# Armor_Plate_V2_1.net
KiCad netlist of a schematic drawn in Altium Designer
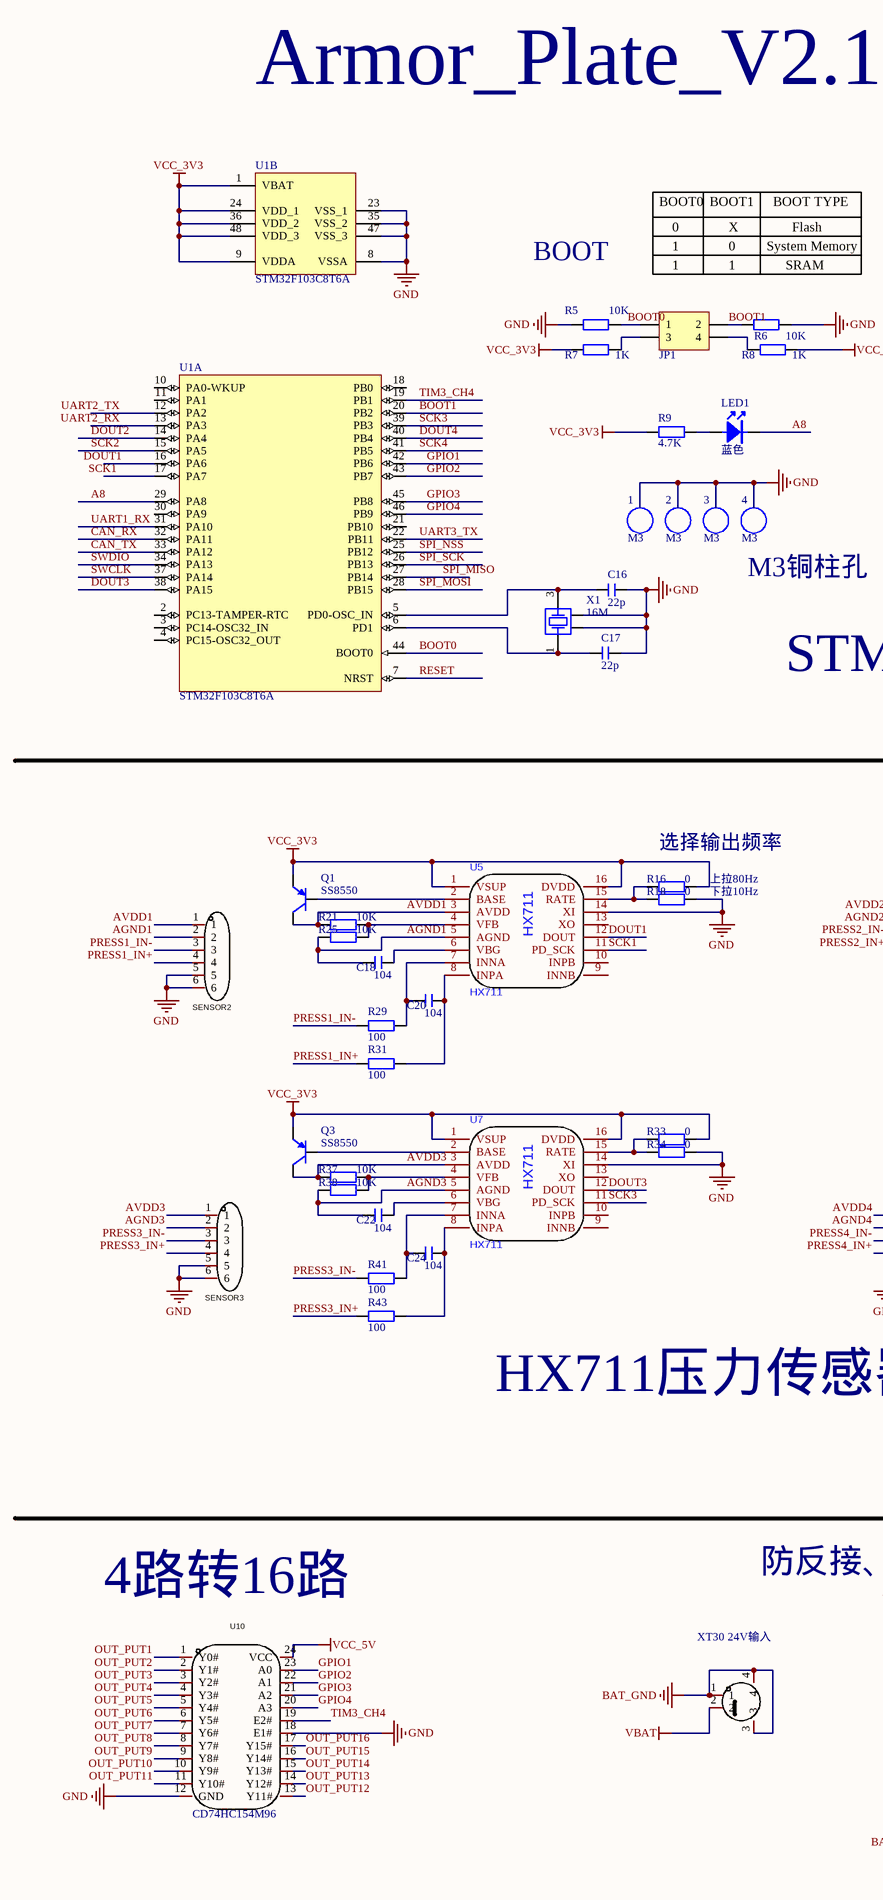
[diagram p0: Armor_Plate_V2.1.SchDoc, left]
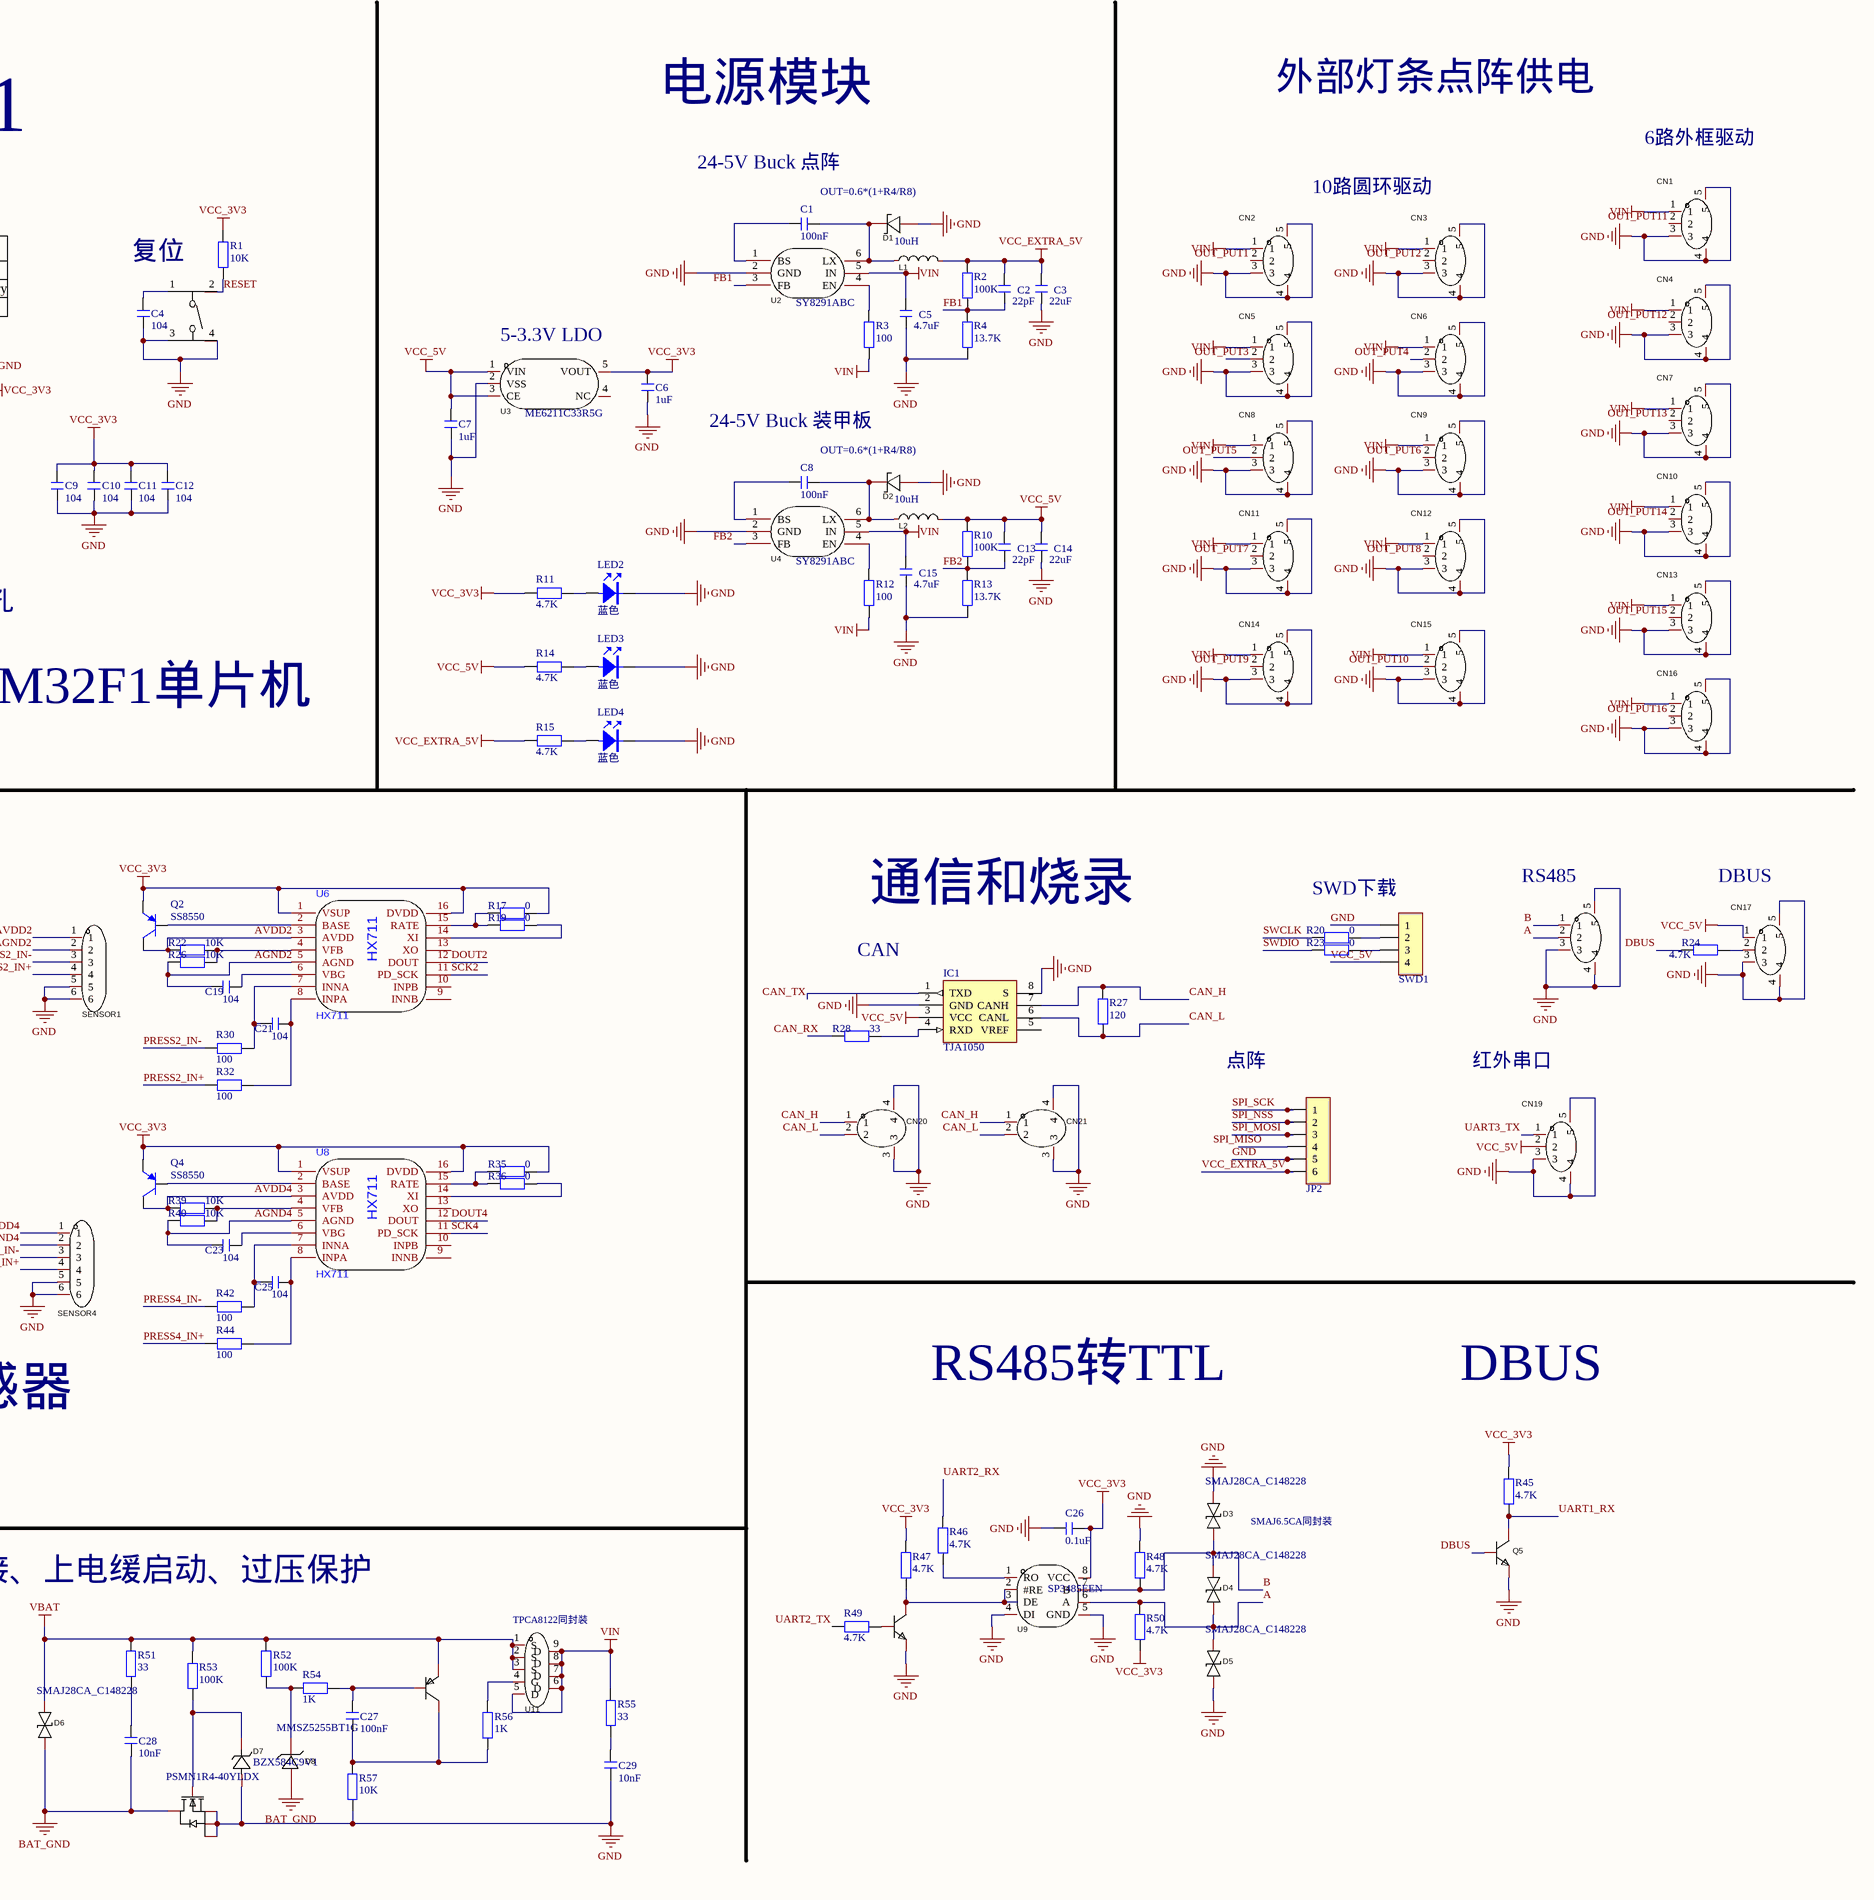
[diagram p1: Armor_Plate_V2.1.SchDoc, right]

(export (version "E")
  (design (tool "Eeschema 10.0.6"))
  (components
    (comp (ref "1")
      (value "M3")
      (footprint "M3 125X200")
      (description "铜柱孔")
      (libsource (lib "10 - 未分类元器件") (part "M3"))
    )
    (comp (ref "2")
      (value "M3")
      (footprint "M3 125X200")
      (description "铜柱孔")
      (libsource (lib "10 - 未分类元器件") (part "M3"))
    )
    (comp (ref "3")
      (value "M3")
      (footprint "M3 125X200")
      (description "铜柱孔")
      (libsource (lib "10 - 未分类元器件") (part "M3"))
    )
    (comp (ref "4")
      (value "M3")
      (footprint "M3 125X200")
      (description "铜柱孔")
      (libsource (lib "10 - 未分类元器件") (part "M3"))
    )
    (comp (ref "C1")
      (value "100nF")
      (footprint "C 0603_L")
      (description "贴片电容")
      (libsource (lib "01 - 电容-电阻-电感") (part "C"))
    )
    (comp (ref "C2")
      (value "22pF")
      (footprint "C 0603_L")
      (description "贴片电容")
      (libsource (lib "01 - 电容-电阻-电感") (part "C"))
    )
    (comp (ref "C3")
      (value "22uF")
      (footprint "C 0603_L")
      (description "贴片电容")
      (libsource (lib "01 - 电容-电阻-电感") (part "C"))
    )
    (comp (ref "C4")
      (value "104")
      (footprint "C 0603_L")
      (description "贴片电容")
      (libsource (lib "01 - 电容-电阻-电感") (part "C"))
    )
    (comp (ref "C5")
      (value "4.7uF")
      (footprint "C 0603_L")
      (description "贴片电容")
      (libsource (lib "01 - 电容-电阻-电感") (part "C"))
    )
    (comp (ref "C6")
      (value "1uF")
      (footprint "C 0603_L")
      (description "贴片电容")
      (libsource (lib "01 - 电容-电阻-电感") (part "C"))
    )
    (comp (ref "C7")
      (value "1uF")
      (footprint "C 0603_L")
      (description "贴片电容")
      (libsource (lib "01 - 电容-电阻-电感") (part "C"))
    )
    (comp (ref "C8")
      (value "100nF")
      (footprint "C 0603_L")
      (description "贴片电容")
      (libsource (lib "01 - 电容-电阻-电感") (part "C"))
    )
    (comp (ref "C9")
      (value "104")
      (footprint "C 0603_L")
      (description "贴片电容")
      (libsource (lib "01 - 电容-电阻-电感") (part "C"))
    )
    (comp (ref "C10")
      (value "104")
      (footprint "C 0603_L")
      (description "贴片电容")
      (libsource (lib "01 - 电容-电阻-电感") (part "C"))
    )
    (comp (ref "C11")
      (value "104")
      (footprint "C 0603_L")
      (description "贴片电容")
      (libsource (lib "01 - 电容-电阻-电感") (part "C"))
    )
    (comp (ref "C12")
      (value "104")
      (footprint "C 0603_L")
      (description "贴片电容")
      (libsource (lib "01 - 电容-电阻-电感") (part "C"))
    )
    (comp (ref "C13")
      (value "22pF")
      (footprint "C 0603_L")
      (description "贴片电容")
      (libsource (lib "01 - 电容-电阻-电感") (part "C"))
    )
    (comp (ref "C14")
      (value "22uF")
      (footprint "C 0603_L")
      (description "贴片电容")
      (libsource (lib "01 - 电容-电阻-电感") (part "C"))
    )
    (comp (ref "C15")
      (value "4.7uF")
      (footprint "C 0603_L")
      (description "贴片电容")
      (libsource (lib "01 - 电容-电阻-电感") (part "C"))
    )
    (comp (ref "C16")
      (value "22p")
      (footprint "C 0603_L")
      (description "贴片电容")
      (libsource (lib "01 - 电容-电阻-电感") (part "C"))
    )
    (comp (ref "C17")
      (value "22p")
      (footprint "C 0603_L")
      (description "贴片电容")
      (libsource (lib "01 - 电容-电阻-电感") (part "C"))
    )
    (comp (ref "C18")
      (value "104")
      (footprint "C 0603_L")
      (description "贴片电容")
      (libsource (lib "01 - 电容-电阻-电感") (part "C"))
    )
    (comp (ref "C19")
      (value "104")
      (footprint "C 0603_L")
      (description "贴片电容")
      (libsource (lib "01 - 电容-电阻-电感") (part "C"))
    )
    (comp (ref "C20")
      (value "104")
      (footprint "C 0603_L")
      (description "贴片电容")
      (libsource (lib "01 - 电容-电阻-电感") (part "C"))
    )
    (comp (ref "C21")
      (value "104")
      (footprint "C 0603_L")
      (description "贴片电容")
      (libsource (lib "01 - 电容-电阻-电感") (part "C"))
    )
    (comp (ref "C22")
      (value "104")
      (footprint "C 0603_L")
      (description "贴片电容")
      (libsource (lib "01 - 电容-电阻-电感") (part "C"))
    )
    (comp (ref "C23")
      (value "104")
      (footprint "C 0603_L")
      (description "贴片电容")
      (libsource (lib "01 - 电容-电阻-电感") (part "C"))
    )
    (comp (ref "C24")
      (value "104")
      (footprint "C 0603_L")
      (description "贴片电容")
      (libsource (lib "01 - 电容-电阻-电感") (part "C"))
    )
    (comp (ref "C25")
      (value "104")
      (footprint "C 0603_L")
      (description "贴片电容")
      (libsource (lib "01 - 电容-电阻-电感") (part "C"))
    )
    (comp (ref "C26")
      (value "0.1uF")
      (footprint "C 0603_L")
      (description "贴片电容")
      (libsource (lib "01 - 电容-电阻-电感") (part "C"))
    )
    (comp (ref "C27")
      (value "100nF")
      (footprint "C 0603_L")
      (description "贴片电容")
      (libsource (lib "01 - 电容-电阻-电感") (part "C"))
    )
    (comp (ref "C28")
      (value "10nF")
      (footprint "C 0603_L")
      (description "贴片电容")
      (libsource (lib "01 - 电容-电阻-电感") (part "C"))
    )
    (comp (ref "C29")
      (value "10nF")
      (footprint "C 0603_L")
      (description "贴片电容")
      (libsource (lib "01 - 电容-电阻-电感") (part "C"))
    )
    (comp (ref "CN1")
      (value "HX25003-3AWB")
      (footprint "CONN-SMD_3P-P2.50_HX25003-3AWB")
      (fields (field (name "MANUFACTURER") "HX(红星)"))
      (libsource (lib "HX25003-3AWB1_HX25003-3AWB") (part "HX25003-3AWB"))
    )
    (comp (ref "CN2")
      (value "HX25003-3AWB")
      (footprint "CONN-SMD_3P-P2.50_HX25003-3AWB")
      (fields (field (name "MANUFACTURER") "HX(红星)"))
      (libsource (lib "HX25003-3AWB1_HX25003-3AWB") (part "HX25003-3AWB"))
    )
    (comp (ref "CN3")
      (value "HX25003-3AWB")
      (footprint "CONN-SMD_3P-P2.50_HX25003-3AWB")
      (fields (field (name "MANUFACTURER") "HX(红星)"))
      (libsource (lib "HX25003-3AWB1_HX25003-3AWB") (part "HX25003-3AWB"))
    )
    (comp (ref "CN4")
      (value "HX25003-3AWB")
      (footprint "CONN-SMD_3P-P2.50_HX25003-3AWB")
      (fields (field (name "MANUFACTURER") "HX(红星)"))
      (libsource (lib "HX25003-3AWB1_HX25003-3AWB") (part "HX25003-3AWB"))
    )
    (comp (ref "CN5")
      (value "HX25003-3AWB")
      (footprint "CONN-SMD_3P-P2.50_HX25003-3AWB")
      (fields (field (name "MANUFACTURER") "HX(红星)"))
      (libsource (lib "HX25003-3AWB1_HX25003-3AWB") (part "HX25003-3AWB"))
    )
    (comp (ref "CN6")
      (value "HX25003-3AWB")
      (footprint "CONN-SMD_3P-P2.50_HX25003-3AWB")
      (fields (field (name "MANUFACTURER") "HX(红星)"))
      (libsource (lib "HX25003-3AWB1_HX25003-3AWB") (part "HX25003-3AWB"))
    )
    (comp (ref "CN7")
      (value "HX25003-3AWB")
      (footprint "CONN-SMD_3P-P2.50_HX25003-3AWB")
      (fields (field (name "MANUFACTURER") "HX(红星)"))
      (libsource (lib "HX25003-3AWB1_HX25003-3AWB") (part "HX25003-3AWB"))
    )
    (comp (ref "CN8")
      (value "HX25003-3AWB")
      (footprint "CONN-SMD_3P-P2.50_HX25003-3AWB")
      (fields (field (name "MANUFACTURER") "HX(红星)"))
      (libsource (lib "HX25003-3AWB1_HX25003-3AWB") (part "HX25003-3AWB"))
    )
    (comp (ref "CN9")
      (value "HX25003-3AWB")
      (footprint "CONN-SMD_3P-P2.50_HX25003-3AWB")
      (fields (field (name "MANUFACTURER") "HX(红星)"))
      (libsource (lib "HX25003-3AWB1_HX25003-3AWB") (part "HX25003-3AWB"))
    )
    (comp (ref "CN10")
      (value "HX25003-3AWB")
      (footprint "CONN-SMD_3P-P2.50_HX25003-3AWB")
      (fields (field (name "MANUFACTURER") "HX(红星)"))
      (libsource (lib "HX25003-3AWB1_HX25003-3AWB") (part "HX25003-3AWB"))
    )
    (comp (ref "CN11")
      (value "HX25003-3AWB")
      (footprint "CONN-SMD_3P-P2.50_HX25003-3AWB")
      (fields (field (name "MANUFACTURER") "HX(红星)"))
      (libsource (lib "HX25003-3AWB1_HX25003-3AWB") (part "HX25003-3AWB"))
    )
    (comp (ref "CN12")
      (value "HX25003-3AWB")
      (footprint "CONN-SMD_3P-P2.50_HX25003-3AWB")
      (fields (field (name "MANUFACTURER") "HX(红星)"))
      (libsource (lib "HX25003-3AWB1_HX25003-3AWB") (part "HX25003-3AWB"))
    )
    (comp (ref "CN13")
      (value "HX25003-3AWB")
      (footprint "CONN-SMD_3P-P2.50_HX25003-3AWB")
      (fields (field (name "MANUFACTURER") "HX(红星)"))
      (libsource (lib "HX25003-3AWB1_HX25003-3AWB") (part "HX25003-3AWB"))
    )
    (comp (ref "CN14")
      (value "HX25003-3AWB")
      (footprint "CONN-SMD_3P-P2.50_HX25003-3AWB")
      (fields (field (name "MANUFACTURER") "HX(红星)"))
      (libsource (lib "HX25003-3AWB1_HX25003-3AWB") (part "HX25003-3AWB"))
    )
    (comp (ref "CN15")
      (value "HX25003-3AWB")
      (footprint "CONN-SMD_3P-P2.50_HX25003-3AWB")
      (fields (field (name "MANUFACTURER") "HX(红星)"))
      (libsource (lib "HX25003-3AWB1_HX25003-3AWB") (part "HX25003-3AWB"))
    )
    (comp (ref "CN16")
      (value "HX25003-3AWB")
      (footprint "CONN-SMD_3P-P2.50_HX25003-3AWB")
      (fields (field (name "MANUFACTURER") "HX(红星)"))
      (libsource (lib "HX25003-3AWB1_HX25003-3AWB") (part "HX25003-3AWB"))
    )
    (comp (ref "CN17")
      (value "HX25003-3AWB")
      (footprint "CONN-SMD_3P-P2.50_HX25003-3AWB")
      (fields (field (name "MANUFACTURER") "HX(红星)"))
      (libsource (lib "HX25003-3AWB1_HX25003-3AWB") (part "HX25003-3AWB"))
    )
    (comp (ref "CN18")
      (value "HX25003-3AWB")
      (footprint "CONN-SMD_3P-P2.50_HX25003-3AWB")
      (fields (field (name "MANUFACTURER") "HX(红星)"))
      (libsource (lib "HX25003-3AWB1_HX25003-3AWB") (part "HX25003-3AWB"))
    )
    (comp (ref "CN19")
      (value "HX25003-3AWB")
      (footprint "CONN-SMD_3P-P2.50_HX25003-3AWB")
      (fields (field (name "MANUFACTURER") "HX(红星)"))
      (libsource (lib "HX25003-3AWB1_HX25003-3AWB") (part "HX25003-3AWB"))
    )
    (comp (ref "CN20")
      (value "A1257WR-S-2P")
      (footprint "CONN-SMD_A1257WR-S-2P")
      (fields (field (name "MANUFACTURER") "CJT(长江连接器)"))
      (libsource (lib "A1257WR-S-2P1_A1257WR-S-2P") (part "A1257WR-S-2P"))
    )
    (comp (ref "CN21")
      (value "A1257WR-S-2P")
      (footprint "CONN-SMD_A1257WR-S-2P")
      (fields (field (name "MANUFACTURER") "CJT(长江连接器)"))
      (libsource (lib "A1257WR-S-2P1_A1257WR-S-2P") (part "A1257WR-S-2P"))
    )
    (comp (ref "CN22")
      (value "XT30PW-M")
      (footprint "CONN-TH_XT30PW-M")
      (fields (field (name "MANUFACTURER") "AMASS(艾迈斯)"))
      (libsource (lib "XT30PW-M1_XT30PW-M") (part "XT30PW-M"))
    )
    (comp (ref "D1")
      (value "1N5819WS_C191023")
      (footprint "SOD-323_L1.8-W1.3-LS2.5-RD")
      (fields (field (name "MANUFACTURER") "Hottech(合科泰)") (field (name "MANUFACTURER PART") "1N5819WS"))
      (libsource (lib "1N5819WS1_1N5819WS") (part "1N5819WS_C191023"))
    )
    (comp (ref "D2")
      (value "1N5819WS_C191023")
      (footprint "SOD-323_L1.8-W1.3-LS2.5-RD")
      (fields (field (name "MANUFACTURER") "Hottech(合科泰)") (field (name "MANUFACTURER PART") "1N5819WS"))
      (libsource (lib "1N5819WS1_1N5819WS") (part "1N5819WS_C191023"))
    )
    (comp (ref "D3")
      (value "SMAJ28CA_C148228")
      (footprint "SMA_L4.4-W2.6-LS5.0-BI")
      (fields (field (name "MANUFACTURER") "Littelfuse(美国力特)") (field (name "MANUFACTURER PART") "SMAJ28CA"))
      (libsource (lib "SMAJ28CA-C1482281_SMAJ28CA-C148228") (part "SMAJ28CA_C148228"))
    )
    (comp (ref "D4")
      (value "SMAJ28CA_C148228")
      (footprint "SMA_L4.4-W2.6-LS5.0-BI")
      (fields (field (name "MANUFACTURER") "Littelfuse(美国力特)") (field (name "MANUFACTURER PART") "SMAJ28CA"))
      (libsource (lib "SMAJ28CA-C1482281_SMAJ28CA-C148228") (part "SMAJ28CA_C148228"))
    )
    (comp (ref "D5")
      (value "SMAJ28CA_C148228")
      (footprint "SMA_L4.4-W2.6-LS5.0-BI")
      (fields (field (name "MANUFACTURER") "Littelfuse(美国力特)") (field (name "MANUFACTURER PART") "SMAJ28CA"))
      (libsource (lib "SMAJ28CA-C1482281_SMAJ28CA-C148228") (part "SMAJ28CA_C148228"))
    )
    (comp (ref "D6")
      (value "SMAJ28CA_C148228")
      (footprint "SMA_L4.4-W2.6-LS5.0-BI")
      (fields (field (name "MANUFACTURER") "Littelfuse(美国力特)") (field (name "MANUFACTURER PART") "SMAJ28CA"))
      (libsource (lib "SMAJ28CA-C1482281_SMAJ28CA-C148228") (part "SMAJ28CA_C148228"))
    )
    (comp (ref "D7")
      (value "BZX584C9V1")
      (footprint "ESC_L1.2-W0.8-LS1.6-RD")
      (fields (field (name "MANUFACTURER") "YANGJIE(扬杰)"))
      (libsource (lib "BZX584C9V11_BZX584C9V1") (part "BZX584C9V1"))
    )
    (comp (ref "D8")
      (value "MMSZ5255BT1G")
      (footprint "SOD-123_L2.7-W1.6-LS3.7-RD")
      (fields (field (name "MANUFACTURER") "onsemi(安森美)") (field (name "TOLERANCE") "±5%"))
      (libsource (lib "MMSZ5255BT1G1_MMSZ5255BT1G") (part "MMSZ5255BT1G"))
    )
    (comp (ref "IC1")
      (value "TJA1050")
      (footprint "SOP8_N")
      (description "CAN总线收发芯片")
      (libsource (lib "39 - 其他芯片类") (part "TJA1050"))
    )
    (comp (ref "JP1")
      (value "Header2X2")
      (footprint "HDR2.54-LI-2x2P")
      (description "2*2P接插件")
      (libsource (lib "18 - 接插件-脚距2.54mm (100mil) ") (part "Header 2X2"))
    )
    (comp (ref "JP2")
      (value "HDR-1X6")
      (footprint "MX 1.25-WS-6P")
      (description "6P接插件")
      (libsource (lib "14 - 接插件-脚距1.25mm") (part "Header 6"))
    )
    (comp (ref "L1")
      (value "10uH")
      (footprint "IND-SMD_L11.2-W10.0")
      (fields
        (field (name "MANUFACTURER") "PSA(信昌电陶)")
        (field (name "MANUFACTURER PART") "MCS10406R8MPY1")
        (field (name "TOLERANCE") "±20%")
      )
      (libsource (lib "MCS1040-6R8MPY11_MCS1040-6R8MPY1") (part "MCS10406R8MPY1"))
    )
    (comp (ref "L2")
      (value "10uH")
      (footprint "IND-SMD_L11.2-W10.0")
      (fields
        (field (name "MANUFACTURER") "PSA(信昌电陶)")
        (field (name "MANUFACTURER PART") "MCS10406R8MPY1")
        (field (name "TOLERANCE") "±20%")
      )
      (libsource (lib "MCS1040-6R8MPY11_MCS1040-6R8MPY1") (part "MCS10406R8MPY1"))
    )
    (comp (ref "LED1")
      (value "蓝色")
      (footprint "LED 0805B")
      (description "贴片LED")
      (libsource (lib "02 - 二极管(LED)-三极管-整流桥") (part "LED-SMD"))
    )
    (comp (ref "LED2")
      (value "蓝色")
      (footprint "LED 0805B")
      (description "贴片LED")
      (libsource (lib "02 - 二极管(LED)-三极管-整流桥") (part "LED-SMD"))
    )
    (comp (ref "LED3")
      (value "蓝色")
      (footprint "LED 0805B")
      (description "贴片LED")
      (libsource (lib "02 - 二极管(LED)-三极管-整流桥") (part "LED-SMD"))
    )
    (comp (ref "LED4")
      (value "蓝色")
      (footprint "LED 0805B")
      (description "贴片LED")
      (libsource (lib "02 - 二极管(LED)-三极管-整流桥") (part "LED-SMD"))
    )
    (comp (ref "Q1")
      (value "SS8550")
      (footprint "SOT23-3N")
      (description "高频放大-PNP型")
      (libsource (lib "02 - 二极管(LED)-三极管-整流桥") (part "8550-SMD"))
    )
    (comp (ref "Q2")
      (value "SS8550")
      (footprint "SOT23-3N")
      (description "高频放大-PNP型")
      (libsource (lib "02 - 二极管(LED)-三极管-整流桥") (part "8550-SMD"))
    )
    (comp (ref "Q3")
      (value "SS8550")
      (footprint "SOT23-3N")
      (description "高频放大-PNP型")
      (libsource (lib "02 - 二极管(LED)-三极管-整流桥") (part "8550-SMD"))
    )
    (comp (ref "Q4")
      (value "SS8550")
      (footprint "SOT23-3N")
      (description "高频放大-PNP型")
      (libsource (lib "02 - 二极管(LED)-三极管-整流桥") (part "8550-SMD"))
    )
    (comp (ref "Q5")
      (value "S8050_C5249674")
      (footprint "SOT-23-3_L2.9-W1.6-P1.90-LS2.8-BR")
      (fields (field (name "MANUFACTURER") "ElecSuper(静芯微）") (field (name "MANUFACTURER PART") "S8050"))
      (libsource (lib "S8050_C52496741_S8050_C5249674") (part "S8050_C5249674"))
    )
    (comp (ref "Q6")
      (value "S8050_C5249674")
      (footprint "SOT-23-3_L2.9-W1.6-P1.90-LS2.8-BR")
      (fields (field (name "MANUFACTURER") "ElecSuper(静芯微）") (field (name "MANUFACTURER PART") "S8050"))
      (libsource (lib "S8050_C52496741_S8050_C5249674") (part "S8050_C5249674"))
    )
    (comp (ref "Q7")
      (value "S8550_C545533")
      (footprint "SOT-23-3_L2.9-W1.6-P1.90-LS2.8-BR")
      (fields (field (name "MANUFACTURER") "UMW(广东友台半导体)") (field (name "MANUFACTURER PART") "S8550"))
      (libsource (lib "S8550_C5455331_S8550_C545533") (part "S8550_C545533"))
    )
    (comp (ref "Q8")
      (value "PSMN1R4-40YLDX")
      (footprint "SOT-669_L4.9-W4.0-P1.27-LS6.0-BR")
      (fields (field (name "MANUFACTURER") "Nexperia(安世)"))
      (libsource (lib "PSMN1R4-40YLDX1_PSMN1R4-40YLDX") (part "PSMN1R4-40YLDX"))
    )
    (comp (ref "R1")
      (value "10K")
      (footprint "R 0603_L")
      (description "贴片电阻")
      (libsource (lib "01 - 电容-电阻-电感") (part "R"))
    )
    (comp (ref "R2")
      (value "100K")
      (footprint "R 0603_L")
      (description "贴片电阻")
      (libsource (lib "01 - 电容-电阻-电感") (part "R"))
    )
    (comp (ref "R3")
      (value "100")
      (footprint "R 0603_L")
      (description "贴片电阻")
      (libsource (lib "01 - 电容-电阻-电感") (part "R"))
    )
    (comp (ref "R4")
      (value "13.7K")
      (footprint "R 0603_L")
      (description "贴片电阻")
      (libsource (lib "01 - 电容-电阻-电感") (part "R"))
    )
    (comp (ref "R5")
      (value "10K")
      (footprint "R 0603_L")
      (description "贴片电阻")
      (libsource (lib "01 - 电容-电阻-电感") (part "R"))
    )
    (comp (ref "R6")
      (value "10K")
      (footprint "R 0603_L")
      (description "贴片电阻")
      (libsource (lib "01 - 电容-电阻-电感") (part "R"))
    )
    (comp (ref "R7")
      (value "1K")
      (footprint "R 0603_L")
      (description "贴片电阻")
      (libsource (lib "01 - 电容-电阻-电感") (part "R"))
    )
    (comp (ref "R8")
      (value "1K")
      (footprint "R 0603_L")
      (description "贴片电阻")
      (libsource (lib "01 - 电容-电阻-电感") (part "R"))
    )
    (comp (ref "R9")
      (value "4.7K")
      (footprint "R 0603_L")
      (description "贴片电阻")
      (libsource (lib "01 - 电容-电阻-电感") (part "R"))
    )
    (comp (ref "R10")
      (value "100K")
      (footprint "R 0603_L")
      (description "贴片电阻")
      (libsource (lib "01 - 电容-电阻-电感") (part "R"))
    )
    (comp (ref "R11")
      (value "4.7K")
      (footprint "R 0603_L")
      (description "贴片电阻")
      (libsource (lib "01 - 电容-电阻-电感") (part "R"))
    )
    (comp (ref "R12")
      (value "100")
      (footprint "R 0603_L")
      (description "贴片电阻")
      (libsource (lib "01 - 电容-电阻-电感") (part "R"))
    )
    (comp (ref "R13")
      (value "13.7K")
      (footprint "R 0603_L")
      (description "贴片电阻")
      (libsource (lib "01 - 电容-电阻-电感") (part "R"))
    )
    (comp (ref "R14")
      (value "4.7K")
      (footprint "R 0603_L")
      (description "贴片电阻")
      (libsource (lib "01 - 电容-电阻-电感") (part "R"))
    )
    (comp (ref "R15")
      (value "4.7K")
      (footprint "R 0603_L")
      (description "贴片电阻")
      (libsource (lib "01 - 电容-电阻-电感") (part "R"))
    )
    (comp (ref "R16")
      (value "0")
      (footprint "R 0603_L")
      (description "贴片电阻")
      (libsource (lib "01 - 电容-电阻-电感") (part "R"))
    )
    (comp (ref "R17")
      (value "0")
      (footprint "R 0603_L")
      (description "贴片电阻")
      (libsource (lib "01 - 电容-电阻-电感") (part "R"))
    )
    (comp (ref "R18")
      (value "0")
      (footprint "R 0603_L")
      (description "贴片电阻")
      (libsource (lib "01 - 电容-电阻-电感") (part "R"))
    )
    (comp (ref "R19")
      (value "0")
      (footprint "R 0603_L")
      (description "贴片电阻")
      (libsource (lib "01 - 电容-电阻-电感") (part "R"))
    )
    (comp (ref "R20")
      (value "0")
      (footprint "R 0603_L")
      (description "贴片电阻")
      (libsource (lib "01 - 电容-电阻-电感") (part "R"))
    )
    (comp (ref "R21")
      (value "10K")
      (footprint "R 0603_L")
      (description "贴片电阻")
      (libsource (lib "01 - 电容-电阻-电感") (part "R"))
    )
    (comp (ref "R22")
      (value "10K")
      (footprint "R 0603_L")
      (description "贴片电阻")
      (libsource (lib "01 - 电容-电阻-电感") (part "R"))
    )
    (comp (ref "R23")
      (value "0")
      (footprint "R 0603_L")
      (description "贴片电阻")
      (libsource (lib "01 - 电容-电阻-电感") (part "R"))
    )
    (comp (ref "R24")
      (value "4.7K")
      (footprint "R 0603_L")
      (description "贴片电阻")
      (libsource (lib "01 - 电容-电阻-电感") (part "R"))
    )
    (comp (ref "R25")
      (value "10K")
      (footprint "R 0603_L")
      (description "贴片电阻")
      (libsource (lib "01 - 电容-电阻-电感") (part "R"))
    )
    (comp (ref "R26")
      (value "10K")
      (footprint "R 0603_L")
      (description "贴片电阻")
      (libsource (lib "01 - 电容-电阻-电感") (part "R"))
    )
    (comp (ref "R27")
      (value "120")
      (footprint "R 0603_L")
      (description "贴片电阻")
      (libsource (lib "01 - 电容-电阻-电感") (part "R"))
    )
    (comp (ref "R28")
      (value "33")
      (footprint "R 0603_L")
      (description "贴片电阻")
      (libsource (lib "01 - 电容-电阻-电感") (part "R"))
    )
    (comp (ref "R29")
      (value "100")
      (footprint "R 0603_L")
      (description "贴片电阻")
      (libsource (lib "01 - 电容-电阻-电感") (part "R"))
    )
    (comp (ref "R30")
      (value "100")
      (footprint "R 0603_L")
      (description "贴片电阻")
      (libsource (lib "01 - 电容-电阻-电感") (part "R"))
    )
    (comp (ref "R31")
      (value "100")
      (footprint "R 0603_L")
      (description "贴片电阻")
      (libsource (lib "01 - 电容-电阻-电感") (part "R"))
    )
    (comp (ref "R32")
      (value "100")
      (footprint "R 0603_L")
      (description "贴片电阻")
      (libsource (lib "01 - 电容-电阻-电感") (part "R"))
    )
    (comp (ref "R33")
      (value "0")
      (footprint "R 0603_L")
      (description "贴片电阻")
      (libsource (lib "01 - 电容-电阻-电感") (part "R"))
    )
    (comp (ref "R34")
      (value "0")
      (footprint "R 0603_L")
      (description "贴片电阻")
      (libsource (lib "01 - 电容-电阻-电感") (part "R"))
    )
    (comp (ref "R35")
      (value "0")
      (footprint "R 0603_L")
      (description "贴片电阻")
      (libsource (lib "01 - 电容-电阻-电感") (part "R"))
    )
    (comp (ref "R36")
      (value "0")
      (footprint "R 0603_L")
      (description "贴片电阻")
      (libsource (lib "01 - 电容-电阻-电感") (part "R"))
    )
    (comp (ref "R37")
      (value "10K")
      (footprint "R 0603_L")
      (description "贴片电阻")
      (libsource (lib "01 - 电容-电阻-电感") (part "R"))
    )
    (comp (ref "R38")
      (value "10K")
      (footprint "R 0603_L")
      (description "贴片电阻")
      (libsource (lib "01 - 电容-电阻-电感") (part "R"))
    )
    (comp (ref "R39")
      (value "10K")
      (footprint "R 0603_L")
      (description "贴片电阻")
      (libsource (lib "01 - 电容-电阻-电感") (part "R"))
    )
    (comp (ref "R40")
      (value "10K")
      (footprint "R 0603_L")
      (description "贴片电阻")
      (libsource (lib "01 - 电容-电阻-电感") (part "R"))
    )
    (comp (ref "R41")
      (value "100")
      (footprint "R 0603_L")
      (description "贴片电阻")
      (libsource (lib "01 - 电容-电阻-电感") (part "R"))
    )
    (comp (ref "R42")
      (value "100")
      (footprint "R 0603_L")
      (description "贴片电阻")
      (libsource (lib "01 - 电容-电阻-电感") (part "R"))
    )
    (comp (ref "R43")
      (value "100")
      (footprint "R 0603_L")
      (description "贴片电阻")
      (libsource (lib "01 - 电容-电阻-电感") (part "R"))
    )
    (comp (ref "R44")
      (value "100")
      (footprint "R 0603_L")
      (description "贴片电阻")
      (libsource (lib "01 - 电容-电阻-电感") (part "R"))
    )
    (comp (ref "R45")
      (value "4.7K")
      (footprint "R 0603_L")
      (description "贴片电阻")
      (libsource (lib "01 - 电容-电阻-电感") (part "R"))
    )
    (comp (ref "R46")
      (value "4.7K")
      (footprint "R 0603_L")
      (description "贴片电阻")
      (libsource (lib "01 - 电容-电阻-电感") (part "R"))
    )
    (comp (ref "R47")
      (value "4.7K")
      (footprint "R 0603_L")
      (description "贴片电阻")
      (libsource (lib "01 - 电容-电阻-电感") (part "R"))
    )
    (comp (ref "R48")
      (value "4.7K")
      (footprint "R 0603_L")
      (description "贴片电阻")
      (libsource (lib "01 - 电容-电阻-电感") (part "R"))
    )
    (comp (ref "R49")
      (value "4.7K")
      (footprint "R 0603_L")
      (description "贴片电阻")
      (libsource (lib "01 - 电容-电阻-电感") (part "R"))
    )
    (comp (ref "R50")
      (value "4.7K")
      (footprint "R 0603_L")
      (description "贴片电阻")
      (libsource (lib "01 - 电容-电阻-电感") (part "R"))
    )
    (comp (ref "R51")
      (value "33")
      (footprint "R 0603_L")
      (description "贴片电阻")
      (libsource (lib "01 - 电容-电阻-电感") (part "R"))
    )
    (comp (ref "R52")
      (value "100K")
      (footprint "R 0603_L")
      (description "贴片电阻")
      (libsource (lib "01 - 电容-电阻-电感") (part "R"))
    )
    (comp (ref "R53")
      (value "100K")
      (footprint "R 0603_L")
      (description "贴片电阻")
      (libsource (lib "01 - 电容-电阻-电感") (part "R"))
    )
    (comp (ref "R54")
      (value "1K")
      (footprint "R 0603_L")
      (description "贴片电阻")
      (libsource (lib "01 - 电容-电阻-电感") (part "R"))
    )
    (comp (ref "R55")
      (value "33")
      (footprint "R 0603_L")
      (description "贴片电阻")
      (libsource (lib "01 - 电容-电阻-电感") (part "R"))
    )
    (comp (ref "R56")
      (value "1K")
      (footprint "R 0603_L")
      (description "贴片电阻")
      (libsource (lib "01 - 电容-电阻-电感") (part "R"))
    )
    (comp (ref "R57")
      (value "10K")
      (footprint "R 0603_L")
      (description "贴片电阻")
      (libsource (lib "01 - 电容-电阻-电感") (part "R"))
    )
    (comp (ref "SENSOR1")
      (value "GH125-S04DCA-00")
      (footprint "CONN-SMD_4P-P1.27_GH125-S04DCA-00")
      (fields (field (name "MANUFACTURER") "JS(钜硕电子)"))
      (libsource (lib "GH125-S04DCA-001_GH125-S04DCA-00") (part "GH125-S04DCA-00"))
    )
    (comp (ref "SENSOR2")
      (value "GH125-S04DCA-00")
      (footprint "CONN-SMD_4P-P1.27_GH125-S04DCA-00")
      (fields (field (name "MANUFACTURER") "JS(钜硕电子)"))
      (libsource (lib "GH125-S04DCA-001_GH125-S04DCA-00") (part "GH125-S04DCA-00"))
    )
    (comp (ref "SENSOR3")
      (value "GH125-S04DCA-00")
      (footprint "CONN-SMD_4P-P1.27_GH125-S04DCA-00")
      (fields (field (name "MANUFACTURER") "JS(钜硕电子)"))
      (libsource (lib "GH125-S04DCA-001_GH125-S04DCA-00") (part "GH125-S04DCA-00"))
    )
    (comp (ref "SENSOR4")
      (value "GH125-S04DCA-00")
      (footprint "CONN-SMD_4P-P1.27_GH125-S04DCA-00")
      (fields (field (name "MANUFACTURER") "JS(钜硕电子)"))
      (libsource (lib "GH125-S04DCA-001_GH125-S04DCA-00") (part "GH125-S04DCA-00"))
    )
    (comp (ref "SW1")
      (value "ST-1188")
      (footprint "SW-SMD_4P-L4.2-W3.2-P2.15-LS5.2")
      (fields (field (name "MANUFACTURER") "RISHENG(日昇)"))
      (libsource (lib "My_SCHLIB") (part "SW-SMD_4P-L4.2-W3.2-P2.15-LS5.2"))
    )
    (comp (ref "SWD1")
      (value "HDR-1X4")
      (footprint "MX 1.25-WS-4P")
      (description "4P接插件")
      (libsource (lib "14 - 接插件-脚距1.25mm") (part "Header 4"))
    )
    (comp (ref "U1")
      (value "STM32F103C8T6A")
      (footprint "LQFP48 7X7_N")
      (libsource (lib "28 - STM32系列单片机") (part "STM32F103C8T6"))
    )
    (comp (ref "U2")
      (value "SY8291ABC")
      (footprint "SOT-23-6_L2.9-W1.6-P0.95-LS2.8-BR")
      (fields (field (name "MANUFACTURER") "silergy(矽力杰)"))
      (libsource (lib "SY8291ABC1_SY8291ABC") (part "SY8291ABC"))
    )
    (comp (ref "U3")
      (value "ME6211C33R5G")
      (footprint "SOT-23-5_L3.0-W1.7-P0.95-LS2.8-BR")
      (fields (field (name "MANUFACTURER") "MICRONE(南京微盟)"))
      (libsource (lib "ME6211C33R5G1_ME6211C33R5G") (part "ME6211C33R5G"))
    )
    (comp (ref "U4")
      (value "SY8291ABC")
      (footprint "SOT-23-6_L2.9-W1.6-P0.95-LS2.8-BR")
      (fields (field (name "MANUFACTURER") "silergy(矽力杰)"))
      (libsource (lib "SY8291ABC1_SY8291ABC") (part "SY8291ABC"))
    )
    (comp (ref "U5")
      (value "HX711")
      (footprint "SOP-16_L10.0-W3.9-P1.27-LS6.0-BL")
      (libsource (lib "My_SCHLIB") (part "HX711"))
    )
    (comp (ref "U6")
      (value "HX711")
      (footprint "SOP-16_L10.0-W3.9-P1.27-LS6.0-BL")
      (libsource (lib "My_SCHLIB") (part "HX711"))
    )
    (comp (ref "U7")
      (value "HX711")
      (footprint "SOP-16_L10.0-W3.9-P1.27-LS6.0-BL")
      (libsource (lib "My_SCHLIB") (part "HX711"))
    )
    (comp (ref "U8")
      (value "HX711")
      (footprint "SOP-16_L10.0-W3.9-P1.27-LS6.0-BL")
      (libsource (lib "My_SCHLIB") (part "HX711"))
    )
    (comp (ref "U9")
      (value "SP3485EEN")
      (footprint "SOP-8_L5.0-W4.0-P1.27-LS6.0-BL")
      (fields (field (name "MANUFACTURER") "UMW(广东友台半导体)"))
      (libsource (lib "SP3485EEN1_SP3485EEN") (part "SP3485EEN"))
    )
    (comp (ref "U10")
      (value "CD74HC154M96")
      (footprint "SOIC-24_L15.4-W7.5-P1.27-LS10.3-BL")
      (fields (field (name "MANUFACTURER") "TI(德州仪器)"))
      (libsource (lib "CD74HC154M961_CD74HC154M96") (part "CD74HC154M96"))
    )
    (comp (ref "U11")
      (value "TPCA8122")
      (footprint "DFN-8_L5.8-W4.9-P1.27-LS6.0-BL-1")
      (fields (field (name "MANUFACTURER") "AGM-Semi(芯控源)") (field (name "MANUFACTURER PART") "AGM402A1"))
      (libsource (lib "AGM402A11_AGM402A1") (part "AGM402A1"))
    )
    (comp (ref "X1")
      (value "16M")
      (footprint "OSC 3225-4P")
      (description "4脚无源晶振")
      (libsource (lib "03 - 按键-开关-晶振-蜂鸣器") (part "XTAL-4P"))
    )
  )
  (nets
    (net (code "1") (name "/A") (class "Default")
      (node (ref "CN18") (pin "2") (pinfunction "2_2") (pintype "passive"))
      (node (ref "D4") (pin "1") (pinfunction "1_1") (pintype "passive"))
      (node (ref "D5") (pin "2") (pinfunction "2_2") (pintype "passive"))
      (node (ref "R50") (pin "2") (pinfunction "2_2") (pintype "passive"))
      (node (ref "U9") (pin "6") (pinfunction "A_6") (pintype "passive"))
    )
    (net (code "2") (name "/A8") (class "Default")
      (node (ref "LED1") (pin "2") (pinfunction "K_2") (pintype "passive"))
      (node (ref "U1") (pin "29") (pinfunction "PA8_29") (pintype "bidirectional"))
    )
    (net (code "3") (name "/AGND1") (class "Default")
      (node (ref "C18") (pin "2") (pinfunction "2_2") (pintype "passive"))
      (node (ref "R25") (pin "1") (pinfunction "1_1") (pintype "passive"))
      (node (ref "SENSOR2") (pin "2") (pinfunction "2_2") (pintype "passive"))
      (node (ref "U5") (pin "5") (pinfunction "AGND_5") (pintype "passive"))
    )
    (net (code "4") (name "/AGND2") (class "Default")
      (node (ref "C19") (pin "2") (pinfunction "2_2") (pintype "passive"))
      (node (ref "R26") (pin "1") (pinfunction "1_1") (pintype "passive"))
      (node (ref "SENSOR1") (pin "2") (pinfunction "2_2") (pintype "passive"))
      (node (ref "U6") (pin "5") (pinfunction "AGND_5") (pintype "passive"))
    )
    (net (code "5") (name "/AGND3") (class "Default")
      (node (ref "C22") (pin "2") (pinfunction "2_2") (pintype "passive"))
      (node (ref "R38") (pin "1") (pinfunction "1_1") (pintype "passive"))
      (node (ref "SENSOR3") (pin "2") (pinfunction "2_2") (pintype "passive"))
      (node (ref "U7") (pin "5") (pinfunction "AGND_5") (pintype "passive"))
    )
    (net (code "6") (name "/AGND4") (class "Default")
      (node (ref "C23") (pin "2") (pinfunction "2_2") (pintype "passive"))
      (node (ref "R40") (pin "1") (pinfunction "1_1") (pintype "passive"))
      (node (ref "SENSOR4") (pin "2") (pinfunction "2_2") (pintype "passive"))
      (node (ref "U8") (pin "5") (pinfunction "AGND_5") (pintype "passive"))
    )
    (net (code "7") (name "/AVDD1") (class "Default")
      (node (ref "Q1") (pin "3") (pinfunction "C_3") (pintype "passive"))
      (node (ref "R21") (pin "1") (pinfunction "1_1") (pintype "passive"))
      (node (ref "SENSOR2") (pin "1") (pinfunction "1_1") (pintype "passive"))
      (node (ref "U5") (pin "3") (pinfunction "AVDD_3") (pintype "passive"))
    )
    (net (code "8") (name "/AVDD2") (class "Default")
      (node (ref "Q2") (pin "3") (pinfunction "C_3") (pintype "passive"))
      (node (ref "R22") (pin "1") (pinfunction "1_1") (pintype "passive"))
      (node (ref "SENSOR1") (pin "1") (pinfunction "1_1") (pintype "passive"))
      (node (ref "U6") (pin "3") (pinfunction "AVDD_3") (pintype "passive"))
    )
    (net (code "9") (name "/AVDD3") (class "Default")
      (node (ref "Q3") (pin "3") (pinfunction "C_3") (pintype "passive"))
      (node (ref "R37") (pin "1") (pinfunction "1_1") (pintype "passive"))
      (node (ref "SENSOR3") (pin "1") (pinfunction "1_1") (pintype "passive"))
      (node (ref "U7") (pin "3") (pinfunction "AVDD_3") (pintype "passive"))
    )
    (net (code "10") (name "/AVDD4") (class "Default")
      (node (ref "Q4") (pin "3") (pinfunction "C_3") (pintype "passive"))
      (node (ref "R39") (pin "1") (pinfunction "1_1") (pintype "passive"))
      (node (ref "SENSOR4") (pin "1") (pinfunction "1_1") (pintype "passive"))
      (node (ref "U8") (pin "3") (pinfunction "AVDD_3") (pintype "passive"))
    )
    (net (code "11") (name "/B") (class "Default")
      (node (ref "CN18") (pin "1") (pinfunction "1_1") (pintype "passive"))
      (node (ref "D3") (pin "1") (pinfunction "1_1") (pintype "passive"))
      (node (ref "D4") (pin "2") (pinfunction "2_2") (pintype "passive"))
      (node (ref "R48") (pin "1") (pinfunction "1_1") (pintype "passive"))
      (node (ref "U9") (pin "7") (pinfunction "B_7") (pintype "passive"))
    )
    (net (code "12") (name "/BOOT0") (class "Default")
      (node (ref "JP1") (pin "1") (pinfunction "1_1") (pintype "passive"))
      (node (ref "R5") (pin "2") (pinfunction "2_2") (pintype "passive"))
      (node (ref "U1") (pin "44") (pinfunction "BOOT0_44") (pintype "input"))
    )
    (net (code "13") (name "/BOOT1") (class "Default")
      (node (ref "JP1") (pin "2") (pinfunction "2_2") (pintype "passive"))
      (node (ref "R6") (pin "1") (pinfunction "1_1") (pintype "passive"))
      (node (ref "U1") (pin "20") (pinfunction "PB2_20") (pintype "bidirectional"))
    )
    (net (code "14") (name "/CAN_H") (class "Default")
      (node (ref "CN20") (pin "1") (pinfunction "1_1") (pintype "passive"))
      (node (ref "CN21") (pin "1") (pinfunction "1_1") (pintype "passive"))
      (node (ref "IC1") (pin "7") (pinfunction "CANH_7") (pintype "passive"))
      (node (ref "R27") (pin "2") (pinfunction "2_2") (pintype "passive"))
    )
    (net (code "15") (name "/CAN_L") (class "Default")
      (node (ref "CN20") (pin "2") (pinfunction "2_2") (pintype "passive"))
      (node (ref "CN21") (pin "2") (pinfunction "2_2") (pintype "passive"))
      (node (ref "IC1") (pin "6") (pinfunction "CANL_6") (pintype "passive"))
      (node (ref "R27") (pin "1") (pinfunction "1_1") (pintype "passive"))
    )
    (net (code "16") (name "/CAN_RX") (class "Default")
      (node (ref "R28") (pin "1") (pinfunction "1_1") (pintype "passive"))
      (node (ref "U1") (pin "32") (pinfunction "PA11_32") (pintype "bidirectional"))
    )
    (net (code "17") (name "/CAN_TX") (class "Default")
      (node (ref "IC1") (pin "1") (pinfunction "TXD_1") (pintype "output"))
      (node (ref "U1") (pin "33") (pinfunction "PA12_33") (pintype "bidirectional"))
    )
    (net (code "18") (name "/DBUS") (class "Default")
      (node (ref "Q5") (pin "1") (pinfunction "B_1") (pintype "passive"))
      (node (ref "R24") (pin "1") (pinfunction "1_1") (pintype "passive"))
    )
    (net (code "19") (name "/DOUT1") (class "Default")
      (node (ref "U1") (pin "16") (pinfunction "PA6_16") (pintype "bidirectional"))
      (node (ref "U5") (pin "12") (pinfunction "DOUT_12") (pintype "passive"))
    )
    (net (code "20") (name "/DOUT2") (class "Default")
      (node (ref "U1") (pin "14") (pinfunction "PA4_14") (pintype "bidirectional"))
      (node (ref "U6") (pin "12") (pinfunction "DOUT_12") (pintype "passive"))
    )
    (net (code "21") (name "/DOUT3") (class "Default")
      (node (ref "U1") (pin "38") (pinfunction "PA15_38") (pintype "bidirectional"))
      (node (ref "U7") (pin "12") (pinfunction "DOUT_12") (pintype "passive"))
    )
    (net (code "22") (name "/DOUT4") (class "Default")
      (node (ref "U1") (pin "40") (pinfunction "PB4_40") (pintype "bidirectional"))
      (node (ref "U8") (pin "12") (pinfunction "DOUT_12") (pintype "passive"))
    )
    (net (code "23") (name "/FB1") (class "Default")
      (node (ref "C2") (pin "1") (pinfunction "1_1") (pintype "passive"))
      (node (ref "R2") (pin "1") (pinfunction "1_1") (pintype "passive"))
      (node (ref "R4") (pin "2") (pinfunction "2_2") (pintype "passive"))
      (node (ref "U2") (pin "3") (pinfunction "FB_3") (pintype "passive"))
    )
    (net (code "24") (name "/FB2") (class "Default")
      (node (ref "C13") (pin "1") (pinfunction "1_1") (pintype "passive"))
      (node (ref "R10") (pin "1") (pinfunction "1_1") (pintype "passive"))
      (node (ref "R13") (pin "2") (pinfunction "2_2") (pintype "passive"))
      (node (ref "U4") (pin "3") (pinfunction "FB_3") (pintype "passive"))
    )
    (net (code "25") (name "/GPIO1") (class "Default")
      (node (ref "U1") (pin "42") (pinfunction "PB6_42") (pintype "bidirectional"))
      (node (ref "U10") (pin "23") (pinfunction "A0_23") (pintype "passive"))
    )
    (net (code "26") (name "/GPIO2") (class "Default")
      (node (ref "U1") (pin "43") (pinfunction "PB7_43") (pintype "bidirectional"))
      (node (ref "U10") (pin "22") (pinfunction "A1_22") (pintype "passive"))
    )
    (net (code "27") (name "/GPIO3") (class "Default")
      (node (ref "U1") (pin "45") (pinfunction "PB8_45") (pintype "bidirectional"))
      (node (ref "U10") (pin "21") (pinfunction "A2_21") (pintype "passive"))
    )
    (net (code "28") (name "/GPIO4") (class "Default")
      (node (ref "U1") (pin "46") (pinfunction "PB9_46") (pintype "bidirectional"))
      (node (ref "U10") (pin "20") (pinfunction "A3_20") (pintype "passive"))
    )
    (net (code "29") (name "/OUT_PUT1") (class "Default")
      (node (ref "CN2") (pin "2") (pinfunction "2_2") (pintype "passive"))
      (node (ref "U10") (pin "1") (pinfunction "Y0#_1") (pintype "passive"))
    )
    (net (code "30") (name "/OUT_PUT2") (class "Default")
      (node (ref "CN3") (pin "2") (pinfunction "2_2") (pintype "passive"))
      (node (ref "U10") (pin "2") (pinfunction "Y1#_2") (pintype "passive"))
    )
    (net (code "31") (name "/OUT_PUT3") (class "Default")
      (node (ref "CN5") (pin "2") (pinfunction "2_2") (pintype "passive"))
      (node (ref "U10") (pin "3") (pinfunction "Y2#_3") (pintype "passive"))
    )
    (net (code "32") (name "/OUT_PUT4") (class "Default")
      (node (ref "CN6") (pin "2") (pinfunction "2_2") (pintype "passive"))
      (node (ref "U10") (pin "4") (pinfunction "Y3#_4") (pintype "passive"))
    )
    (net (code "33") (name "/OUT_PUT5") (class "Default")
      (node (ref "CN8") (pin "2") (pinfunction "2_2") (pintype "passive"))
      (node (ref "U10") (pin "5") (pinfunction "Y4#_5") (pintype "passive"))
    )
    (net (code "34") (name "/OUT_PUT6") (class "Default")
      (node (ref "CN9") (pin "2") (pinfunction "2_2") (pintype "passive"))
      (node (ref "U10") (pin "6") (pinfunction "Y5#_6") (pintype "passive"))
    )
    (net (code "35") (name "/OUT_PUT7") (class "Default")
      (node (ref "CN11") (pin "2") (pinfunction "2_2") (pintype "passive"))
      (node (ref "U10") (pin "7") (pinfunction "Y6#_7") (pintype "passive"))
    )
    (net (code "36") (name "/OUT_PUT8") (class "Default")
      (node (ref "CN12") (pin "2") (pinfunction "2_2") (pintype "passive"))
      (node (ref "U10") (pin "8") (pinfunction "Y7#_8") (pintype "passive"))
    )
    (net (code "37") (name "/OUT_PUT9") (class "Default")
      (node (ref "CN14") (pin "2") (pinfunction "2_2") (pintype "passive"))
      (node (ref "U10") (pin "9") (pinfunction "Y8#_9") (pintype "passive"))
    )
    (net (code "38") (name "/OUT_PUT10") (class "Default")
      (node (ref "CN15") (pin "2") (pinfunction "2_2") (pintype "passive"))
      (node (ref "U10") (pin "10") (pinfunction "Y9#_10") (pintype "passive"))
    )
    (net (code "39") (name "/OUT_PUT11") (class "Default")
      (node (ref "CN1") (pin "2") (pinfunction "2_2") (pintype "passive"))
      (node (ref "U10") (pin "11") (pinfunction "Y10#_11") (pintype "passive"))
    )
    (net (code "40") (name "/OUT_PUT12") (class "Default")
      (node (ref "CN4") (pin "2") (pinfunction "2_2") (pintype "passive"))
      (node (ref "U10") (pin "13") (pinfunction "Y11#_13") (pintype "passive"))
    )
    (net (code "41") (name "/OUT_PUT13") (class "Default")
      (node (ref "CN7") (pin "2") (pinfunction "2_2") (pintype "passive"))
      (node (ref "U10") (pin "14") (pinfunction "Y12#_14") (pintype "passive"))
    )
    (net (code "42") (name "/OUT_PUT14") (class "Default")
      (node (ref "CN10") (pin "2") (pinfunction "2_2") (pintype "passive"))
      (node (ref "U10") (pin "15") (pinfunction "Y13#_15") (pintype "passive"))
    )
    (net (code "43") (name "/OUT_PUT15") (class "Default")
      (node (ref "CN13") (pin "2") (pinfunction "2_2") (pintype "passive"))
      (node (ref "U10") (pin "16") (pinfunction "Y14#_16") (pintype "passive"))
    )
    (net (code "44") (name "/OUT_PUT16") (class "Default")
      (node (ref "CN16") (pin "2") (pinfunction "2_2") (pintype "passive"))
      (node (ref "U10") (pin "17") (pinfunction "Y15#_17") (pintype "passive"))
    )
    (net (code "45") (name "/PRESS1_IN+") (class "Default")
      (node (ref "R31") (pin "2") (pinfunction "2_2") (pintype "passive"))
      (node (ref "SENSOR2") (pin "4") (pinfunction "4_4") (pintype "passive"))
    )
    (net (code "46") (name "/PRESS1_IN-") (class "Default")
      (node (ref "R29") (pin "1") (pinfunction "1_1") (pintype "passive"))
      (node (ref "SENSOR2") (pin "3") (pinfunction "3_3") (pintype "passive"))
    )
    (net (code "47") (name "/PRESS2_IN+") (class "Default")
      (node (ref "R32") (pin "2") (pinfunction "2_2") (pintype "passive"))
      (node (ref "SENSOR1") (pin "4") (pinfunction "4_4") (pintype "passive"))
    )
    (net (code "48") (name "/PRESS2_IN-") (class "Default")
      (node (ref "R30") (pin "1") (pinfunction "1_1") (pintype "passive"))
      (node (ref "SENSOR1") (pin "3") (pinfunction "3_3") (pintype "passive"))
    )
    (net (code "49") (name "/PRESS3_IN+") (class "Default")
      (node (ref "R43") (pin "2") (pinfunction "2_2") (pintype "passive"))
      (node (ref "SENSOR3") (pin "4") (pinfunction "4_4") (pintype "passive"))
    )
    (net (code "50") (name "/PRESS3_IN-") (class "Default")
      (node (ref "R41") (pin "1") (pinfunction "1_1") (pintype "passive"))
      (node (ref "SENSOR3") (pin "3") (pinfunction "3_3") (pintype "passive"))
    )
    (net (code "51") (name "/PRESS4_IN+") (class "Default")
      (node (ref "R44") (pin "2") (pinfunction "2_2") (pintype "passive"))
      (node (ref "SENSOR4") (pin "4") (pinfunction "4_4") (pintype "passive"))
    )
    (net (code "52") (name "/PRESS4_IN-") (class "Default")
      (node (ref "R42") (pin "1") (pinfunction "1_1") (pintype "passive"))
      (node (ref "SENSOR4") (pin "3") (pinfunction "3_3") (pintype "passive"))
    )
    (net (code "53") (name "/RESET") (class "Default")
      (node (ref "R1") (pin "1") (pinfunction "1_1") (pintype "passive"))
      (node (ref "SW1") (pin "2") (pinfunction "2_2") (pintype "passive"))
      (node (ref "U1") (pin "7") (pinfunction "NRST_7") (pintype "bidirectional"))
    )
    (net (code "54") (name "/SCK1") (class "Default")
      (node (ref "U1") (pin "17") (pinfunction "PA7_17") (pintype "bidirectional"))
      (node (ref "U5") (pin "11") (pinfunction "PD_SCK_11") (pintype "passive"))
    )
    (net (code "55") (name "/SCK2") (class "Default")
      (node (ref "U1") (pin "15") (pinfunction "PA5_15") (pintype "bidirectional"))
      (node (ref "U6") (pin "11") (pinfunction "PD_SCK_11") (pintype "passive"))
    )
    (net (code "56") (name "/SCK3") (class "Default")
      (node (ref "U1") (pin "39") (pinfunction "PB3_39") (pintype "bidirectional"))
      (node (ref "U7") (pin "11") (pinfunction "PD_SCK_11") (pintype "passive"))
    )
    (net (code "57") (name "/SCK4") (class "Default")
      (node (ref "U1") (pin "41") (pinfunction "PB5_41") (pintype "bidirectional"))
      (node (ref "U8") (pin "11") (pinfunction "PD_SCK_11") (pintype "passive"))
    )
    (net (code "58") (name "/SPI_MISO") (class "Default")
      (node (ref "JP2") (pin "4") (pinfunction "4_4") (pintype "passive"))
      (node (ref "U1") (pin "27") (pinfunction "PB14_27") (pintype "bidirectional"))
    )
    (net (code "59") (name "/SPI_MOSI") (class "Default")
      (node (ref "JP2") (pin "3") (pinfunction "3_3") (pintype "passive"))
      (node (ref "U1") (pin "28") (pinfunction "PB15_28") (pintype "bidirectional"))
    )
    (net (code "60") (name "/SPI_NSS") (class "Default")
      (node (ref "JP2") (pin "2") (pinfunction "2_2") (pintype "passive"))
      (node (ref "U1") (pin "25") (pinfunction "PB12_25") (pintype "bidirectional"))
    )
    (net (code "61") (name "/SPI_SCK") (class "Default")
      (node (ref "JP2") (pin "1") (pinfunction "1_1") (pintype "passive"))
      (node (ref "U1") (pin "26") (pinfunction "PB13_26") (pintype "bidirectional"))
    )
    (net (code "62") (name "/SWCLK") (class "Default")
      (node (ref "R20") (pin "1") (pinfunction "1_1") (pintype "passive"))
      (node (ref "U1") (pin "37") (pinfunction "PA14_37") (pintype "bidirectional"))
    )
    (net (code "63") (name "/SWDIO") (class "Default")
      (node (ref "R23") (pin "1") (pinfunction "1_1") (pintype "passive"))
      (node (ref "U1") (pin "34") (pinfunction "PA13_34") (pintype "bidirectional"))
    )
    (net (code "64") (name "/TIM3_CH4") (class "Default")
      (node (ref "U1") (pin "19") (pinfunction "PB1_19") (pintype "bidirectional"))
      (node (ref "U10") (pin "19") (pinfunction "E2#_19") (pintype "passive"))
    )
    (net (code "65") (name "/UART1_RX") (class "Default")
      (node (ref "Q5") (pin "3") (pinfunction "C_3") (pintype "passive"))
      (node (ref "R45") (pin "1") (pinfunction "1_1") (pintype "passive"))
      (node (ref "U1") (pin "31") (pinfunction "PA10_31") (pintype "bidirectional"))
    )
    (net (code "66") (name "/UART2_RX") (class "Default")
      (node (ref "R46") (pin "2") (pinfunction "2_2") (pintype "passive"))
      (node (ref "U1") (pin "13") (pinfunction "PA3_13") (pintype "bidirectional"))
    )
    (net (code "67") (name "/UART2_TX") (class "Default")
      (node (ref "R49") (pin "1") (pinfunction "1_1") (pintype "passive"))
      (node (ref "U1") (pin "12") (pinfunction "PA2_12") (pintype "bidirectional"))
    )
    (net (code "68") (name "/UART3_TX") (class "Default")
      (node (ref "CN19") (pin "1") (pinfunction "1_1") (pintype "passive"))
      (node (ref "U1") (pin "22") (pinfunction "PB11_22") (pintype "bidirectional"))
    )
    (net (code "69") (name "BAT_GND") (class "Default")
      (node (ref "C28") (pin "2") (pinfunction "2_2") (pintype "passive"))
      (node (ref "CN22") (pin "1") (pinfunction "1_1") (pintype "passive"))
      (node (ref "CN22") (pin "3") (pinfunction "3_3") (pintype "passive"))
      (node (ref "CN22") (pin "4") (pinfunction "4_4") (pintype "passive"))
      (node (ref "D6") (pin "1") (pinfunction "1_1") (pintype "passive"))
      (node (ref "D8") (pin "2") (pinfunction "A_2") (pintype "passive"))
      (node (ref "Q8") (pin "5") (pinfunction "D_5") (pintype "passive"))
    )
    (net (code "70") (name "GND") (class "Default")
      (node (ref "C10") (pin "1") (pinfunction "1_1") (pintype "passive"))
      (node (ref "C11") (pin "1") (pinfunction "1_1") (pintype "passive"))
      (node (ref "C12") (pin "1") (pinfunction "1_1") (pintype "passive"))
      (node (ref "C14") (pin "1") (pinfunction "1_1") (pintype "passive"))
      (node (ref "C15") (pin "1") (pinfunction "1_1") (pintype "passive"))
      (node (ref "C16") (pin "2") (pinfunction "2_2") (pintype "passive"))
      (node (ref "C17") (pin "2") (pinfunction "2_2") (pintype "passive"))
      (node (ref "C26") (pin "1") (pinfunction "1_1") (pintype "passive"))
      (node (ref "C29") (pin "2") (pinfunction "2_2") (pintype "passive"))
      (node (ref "C3") (pin "1") (pinfunction "1_1") (pintype "passive"))
      (node (ref "C4") (pin "1") (pinfunction "1_1") (pintype "passive"))
      (node (ref "C5") (pin "1") (pinfunction "1_1") (pintype "passive"))
      (node (ref "C6") (pin "1") (pinfunction "1_1") (pintype "passive"))
      (node (ref "C7") (pin "1") (pinfunction "1_1") (pintype "passive"))
      (node (ref "C9") (pin "1") (pinfunction "1_1") (pintype "passive"))
      (node (ref "CN1") (pin "3") (pinfunction "3_3") (pintype "passive"))
      (node (ref "CN1") (pin "4") (pinfunction "4_4") (pintype "passive"))
      (node (ref "CN1") (pin "5") (pinfunction "5_5") (pintype "passive"))
      (node (ref "CN10") (pin "3") (pinfunction "3_3") (pintype "passive"))
      (node (ref "CN10") (pin "4") (pinfunction "4_4") (pintype "passive"))
      (node (ref "CN10") (pin "5") (pinfunction "5_5") (pintype "passive"))
      (node (ref "CN11") (pin "3") (pinfunction "3_3") (pintype "passive"))
      (node (ref "CN11") (pin "4") (pinfunction "4_4") (pintype "passive"))
      (node (ref "CN11") (pin "5") (pinfunction "5_5") (pintype "passive"))
      (node (ref "CN12") (pin "3") (pinfunction "3_3") (pintype "passive"))
      (node (ref "CN12") (pin "4") (pinfunction "4_4") (pintype "passive"))
      (node (ref "CN12") (pin "5") (pinfunction "5_5") (pintype "passive"))
      (node (ref "CN13") (pin "3") (pinfunction "3_3") (pintype "passive"))
      (node (ref "CN13") (pin "4") (pinfunction "4_4") (pintype "passive"))
      (node (ref "CN13") (pin "5") (pinfunction "5_5") (pintype "passive"))
      (node (ref "CN14") (pin "3") (pinfunction "3_3") (pintype "passive"))
      (node (ref "CN14") (pin "4") (pinfunction "4_4") (pintype "passive"))
      (node (ref "CN14") (pin "5") (pinfunction "5_5") (pintype "passive"))
      (node (ref "CN15") (pin "3") (pinfunction "3_3") (pintype "passive"))
      (node (ref "CN15") (pin "4") (pinfunction "4_4") (pintype "passive"))
      (node (ref "CN15") (pin "5") (pinfunction "5_5") (pintype "passive"))
      (node (ref "CN16") (pin "3") (pinfunction "3_3") (pintype "passive"))
      (node (ref "CN16") (pin "4") (pinfunction "4_4") (pintype "passive"))
      (node (ref "CN16") (pin "5") (pinfunction "5_5") (pintype "passive"))
      (node (ref "CN17") (pin "3") (pinfunction "3_3") (pintype "passive"))
      (node (ref "CN17") (pin "4") (pinfunction "4_4") (pintype "passive"))
      (node (ref "CN17") (pin "5") (pinfunction "5_5") (pintype "passive"))
      (node (ref "CN18") (pin "3") (pinfunction "3_3") (pintype "passive"))
      (node (ref "CN18") (pin "4") (pinfunction "4_4") (pintype "passive"))
      (node (ref "CN18") (pin "5") (pinfunction "5_5") (pintype "passive"))
      (node (ref "CN19") (pin "3") (pinfunction "3_3") (pintype "passive"))
      (node (ref "CN19") (pin "4") (pinfunction "4_4") (pintype "passive"))
      (node (ref "CN19") (pin "5") (pinfunction "5_5") (pintype "passive"))
      (node (ref "CN2") (pin "3") (pinfunction "3_3") (pintype "passive"))
      (node (ref "CN2") (pin "4") (pinfunction "4_4") (pintype "passive"))
      (node (ref "CN2") (pin "5") (pinfunction "5_5") (pintype "passive"))
      (node (ref "CN20") (pin "3") (pinfunction "3_3") (pintype "passive"))
      (node (ref "CN20") (pin "4") (pinfunction "4_4") (pintype "passive"))
      (node (ref "CN21") (pin "3") (pinfunction "3_3") (pintype "passive"))
      (node (ref "CN21") (pin "4") (pinfunction "4_4") (pintype "passive"))
      (node (ref "CN3") (pin "3") (pinfunction "3_3") (pintype "passive"))
      (node (ref "CN3") (pin "4") (pinfunction "4_4") (pintype "passive"))
      (node (ref "CN3") (pin "5") (pinfunction "5_5") (pintype "passive"))
      (node (ref "CN4") (pin "3") (pinfunction "3_3") (pintype "passive"))
      (node (ref "CN4") (pin "4") (pinfunction "4_4") (pintype "passive"))
      (node (ref "CN4") (pin "5") (pinfunction "5_5") (pintype "passive"))
      (node (ref "CN5") (pin "3") (pinfunction "3_3") (pintype "passive"))
      (node (ref "CN5") (pin "4") (pinfunction "4_4") (pintype "passive"))
      (node (ref "CN5") (pin "5") (pinfunction "5_5") (pintype "passive"))
      (node (ref "CN6") (pin "3") (pinfunction "3_3") (pintype "passive"))
      (node (ref "CN6") (pin "4") (pinfunction "4_4") (pintype "passive"))
      (node (ref "CN6") (pin "5") (pinfunction "5_5") (pintype "passive"))
      (node (ref "CN7") (pin "3") (pinfunction "3_3") (pintype "passive"))
      (node (ref "CN7") (pin "4") (pinfunction "4_4") (pintype "passive"))
      (node (ref "CN7") (pin "5") (pinfunction "5_5") (pintype "passive"))
      (node (ref "CN8") (pin "3") (pinfunction "3_3") (pintype "passive"))
      (node (ref "CN8") (pin "4") (pinfunction "4_4") (pintype "passive"))
      (node (ref "CN8") (pin "5") (pinfunction "5_5") (pintype "passive"))
      (node (ref "CN9") (pin "3") (pinfunction "3_3") (pintype "passive"))
      (node (ref "CN9") (pin "4") (pinfunction "4_4") (pintype "passive"))
      (node (ref "CN9") (pin "5") (pinfunction "5_5") (pintype "passive"))
      (node (ref "D1") (pin "2") (pinfunction "A_2") (pintype "passive"))
      (node (ref "D2") (pin "2") (pinfunction "A_2") (pintype "passive"))
      (node (ref "D3") (pin "2") (pinfunction "2_2") (pintype "passive"))
      (node (ref "D5") (pin "1") (pinfunction "1_1") (pintype "passive"))
      (node (ref "D7") (pin "2") (pinfunction "A_2") (pintype "passive"))
      (node (ref "IC1") (pin "2") (pinfunction "GND_2") (pintype "passive"))
      (node (ref "IC1") (pin "8") (pinfunction "S_8") (pintype "passive"))
      (node (ref "JP2") (pin "5") (pinfunction "5_5") (pintype "passive"))
      (node (ref "LED2") (pin "2") (pinfunction "K_2") (pintype "passive"))
      (node (ref "LED3") (pin "2") (pinfunction "K_2") (pintype "passive"))
      (node (ref "LED4") (pin "2") (pinfunction "K_2") (pintype "passive"))
      (node (ref "Q5") (pin "2") (pinfunction "E_2") (pintype "passive"))
      (node (ref "Q6") (pin "2") (pinfunction "E_2") (pintype "passive"))
      (node (ref "Q8") (pin "1") (pinfunction "S_1") (pintype "passive"))
      (node (ref "Q8") (pin "2") (pinfunction "S_2") (pintype "passive"))
      (node (ref "Q8") (pin "3") (pinfunction "S_3") (pintype "passive"))
      (node (ref "R13") (pin "1") (pinfunction "1_1") (pintype "passive"))
      (node (ref "R18") (pin "2") (pinfunction "2_2") (pintype "passive"))
      (node (ref "R34") (pin "2") (pinfunction "2_2") (pintype "passive"))
      (node (ref "R4") (pin "1") (pinfunction "1_1") (pintype "passive"))
      (node (ref "R48") (pin "2") (pinfunction "2_2") (pintype "passive"))
      (node (ref "R5") (pin "1") (pinfunction "1_1") (pintype "passive"))
      (node (ref "R57") (pin "2") (pinfunction "2_2") (pintype "passive"))
      (node (ref "R6") (pin "2") (pinfunction "2_2") (pintype "passive"))
      (node (ref "SENSOR1") (pin "5") (pinfunction "5_5") (pintype "passive"))
      (node (ref "SENSOR1") (pin "6") (pinfunction "6_6") (pintype "passive"))
      (node (ref "SENSOR2") (pin "5") (pinfunction "5_5") (pintype "passive"))
      (node (ref "SENSOR2") (pin "6") (pinfunction "6_6") (pintype "passive"))
      (node (ref "SENSOR3") (pin "5") (pinfunction "5_5") (pintype "passive"))
      (node (ref "SENSOR3") (pin "6") (pinfunction "6_6") (pintype "passive"))
      (node (ref "SENSOR4") (pin "5") (pinfunction "5_5") (pintype "passive"))
      (node (ref "SENSOR4") (pin "6") (pinfunction "6_6") (pintype "passive"))
      (node (ref "SW1") (pin "3") (pinfunction "3_3") (pintype "passive"))
      (node (ref "SW1") (pin "4") (pinfunction "4_4") (pintype "passive"))
      (node (ref "SWD1") (pin "1") (pinfunction "1_1") (pintype "passive"))
      (node (ref "U1") (pin "23") (pinfunction "VSS_1_23") (pintype "power_in"))
      (node (ref "U1") (pin "35") (pinfunction "VSS_2_35") (pintype "power_in"))
      (node (ref "U1") (pin "47") (pinfunction "VSS_3_47") (pintype "power_in"))
      (node (ref "U1") (pin "8") (pinfunction "VSSA_8") (pintype "power_in"))
      (node (ref "U10") (pin "12") (pinfunction "GND_12") (pintype "passive"))
      (node (ref "U10") (pin "18") (pinfunction "E1#_18") (pintype "passive"))
      (node (ref "U2") (pin "2") (pinfunction "GND_2") (pintype "passive"))
      (node (ref "U3") (pin "2") (pinfunction "VSS_2") (pintype "passive"))
      (node (ref "U4") (pin "2") (pinfunction "GND_2") (pintype "passive"))
      (node (ref "U5") (pin "14") (pinfunction "XI_14") (pintype "passive"))
      (node (ref "U7") (pin "14") (pinfunction "XI_14") (pintype "passive"))
      (node (ref "U9") (pin "4") (pinfunction "DI_4") (pintype "passive"))
      (node (ref "U9") (pin "5") (pinfunction "GND_5") (pintype "passive"))
      (node (ref "X1") (pin "2") (pinfunction "2_2") (pintype "passive"))
      (node (ref "X1") (pin "4") (pinfunction "4_4") (pintype "passive"))
    )
    (net (code "71") (name "Net-(C4-Pad2)") (class "Default")
      (node (ref "C4") (pin "2") (pinfunction "2_2") (pintype "passive"))
      (node (ref "SW1") (pin "1") (pinfunction "1_1") (pintype "passive"))
    )
    (net (code "72") (name "Net-(C28-Pad1)") (class "Default")
      (node (ref "C28") (pin "1") (pinfunction "1_1") (pintype "passive"))
      (node (ref "R51") (pin "1") (pinfunction "1_1") (pintype "passive"))
    )
    (net (code "73") (name "Net-(C29-Pad1)") (class "Default")
      (node (ref "C29") (pin "1") (pinfunction "1_1") (pintype "passive"))
      (node (ref "R55") (pin "2") (pinfunction "2_2") (pintype "passive"))
    )
    (net (code "74") (name "Net-(CN17-Pad2)") (class "Default")
      (node (ref "CN17") (pin "2") (pinfunction "2_2") (pintype "passive"))
      (node (ref "R24") (pin "2") (pinfunction "2_2") (pintype "passive"))
    )
    (net (code "75") (name "Net-(D1-C)") (class "Default")
      (node (ref "C1") (pin "1") (pinfunction "1_1") (pintype "passive"))
      (node (ref "D1") (pin "1") (pinfunction "C_1") (pintype "passive"))
      (node (ref "L1") (pin "1") (pinfunction "1_1") (pintype "passive"))
      (node (ref "U2") (pin "6") (pinfunction "LX_6") (pintype "passive"))
    )
    (net (code "76") (name "Net-(D2-C)") (class "Default")
      (node (ref "C8") (pin "1") (pinfunction "1_1") (pintype "passive"))
      (node (ref "D2") (pin "1") (pinfunction "C_1") (pintype "passive"))
      (node (ref "L2") (pin "1") (pinfunction "1_1") (pintype "passive"))
      (node (ref "U4") (pin "6") (pinfunction "LX_6") (pintype "passive"))
    )
    (net (code "77") (name "Net-(D7-K)") (class "Default")
      (node (ref "D7") (pin "1") (pinfunction "K_1") (pintype "passive"))
      (node (ref "Q8") (pin "4") (pinfunction "G_4") (pintype "passive"))
      (node (ref "R53") (pin "1") (pinfunction "1_1") (pintype "passive"))
    )
    (net (code "78") (name "Net-(D8-K)") (class "Default")
      (node (ref "D8") (pin "1") (pinfunction "K_1") (pintype "passive"))
      (node (ref "R52") (pin "1") (pinfunction "1_1") (pintype "passive"))
      (node (ref "R54") (pin "2") (pinfunction "2_2") (pintype "passive"))
    )
    (net (code "79") (name "Net-(IC1-RXD)") (class "Default")
      (node (ref "IC1") (pin "4") (pinfunction "RXD_4") (pintype "input"))
      (node (ref "R28") (pin "2") (pinfunction "2_2") (pintype "passive"))
    )
    (net (code "80") (name "Net-(JP1-Pad3)") (class "Default")
      (node (ref "JP1") (pin "3") (pinfunction "3_3") (pintype "passive"))
      (node (ref "R7") (pin "2") (pinfunction "2_2") (pintype "passive"))
    )
    (net (code "81") (name "Net-(JP1-Pad4)") (class "Default")
      (node (ref "JP1") (pin "4") (pinfunction "4_4") (pintype "passive"))
      (node (ref "R8") (pin "1") (pinfunction "1_1") (pintype "passive"))
    )
    (net (code "82") (name "Net-(LED1-A)") (class "Default")
      (node (ref "LED1") (pin "1") (pinfunction "A_1") (pintype "passive"))
      (node (ref "R9") (pin "2") (pinfunction "2_2") (pintype "passive"))
    )
    (net (code "83") (name "Net-(LED2-A)") (class "Default")
      (node (ref "LED2") (pin "1") (pinfunction "A_1") (pintype "passive"))
      (node (ref "R11") (pin "2") (pinfunction "2_2") (pintype "passive"))
    )
    (net (code "84") (name "Net-(LED3-A)") (class "Default")
      (node (ref "LED3") (pin "1") (pinfunction "A_1") (pintype "passive"))
      (node (ref "R14") (pin "2") (pinfunction "2_2") (pintype "passive"))
    )
    (net (code "85") (name "Net-(LED4-A)") (class "Default")
      (node (ref "LED4") (pin "1") (pinfunction "A_1") (pintype "passive"))
      (node (ref "R15") (pin "2") (pinfunction "2_2") (pintype "passive"))
    )
    (net (code "86") (name "Net-(Q1-B)") (class "Default")
      (node (ref "Q1") (pin "1") (pinfunction "B_1") (pintype "passive"))
      (node (ref "U5") (pin "2") (pinfunction "BASE_2") (pintype "passive"))
    )
    (net (code "87") (name "Net-(Q2-B)") (class "Default")
      (node (ref "Q2") (pin "1") (pinfunction "B_1") (pintype "passive"))
      (node (ref "U6") (pin "2") (pinfunction "BASE_2") (pintype "passive"))
    )
    (net (code "88") (name "Net-(Q3-B)") (class "Default")
      (node (ref "Q3") (pin "1") (pinfunction "B_1") (pintype "passive"))
      (node (ref "U7") (pin "2") (pinfunction "BASE_2") (pintype "passive"))
    )
    (net (code "89") (name "Net-(Q4-B)") (class "Default")
      (node (ref "Q4") (pin "1") (pinfunction "B_1") (pintype "passive"))
      (node (ref "U8") (pin "2") (pinfunction "BASE_2") (pintype "passive"))
    )
    (net (code "90") (name "Net-(Q6-B)") (class "Default")
      (node (ref "Q6") (pin "1") (pinfunction "B_1") (pintype "passive"))
      (node (ref "R49") (pin "2") (pinfunction "2_2") (pintype "passive"))
    )
    (net (code "91") (name "Net-(Q6-C)") (class "Default")
      (node (ref "Q6") (pin "3") (pinfunction "C_3") (pintype "passive"))
      (node (ref "R47") (pin "1") (pinfunction "1_1") (pintype "passive"))
      (node (ref "U9") (pin "2") (pinfunction "#RE_2") (pintype "passive"))
      (node (ref "U9") (pin "3") (pinfunction "DE_3") (pintype "passive"))
    )
    (net (code "92") (name "Net-(Q7-B)") (class "Default")
      (node (ref "C27") (pin "1") (pinfunction "1_1") (pintype "passive"))
      (node (ref "Q7") (pin "1") (pinfunction "B_1") (pintype "passive"))
      (node (ref "R54") (pin "1") (pinfunction "1_1") (pintype "passive"))
    )
    (net (code "93") (name "Net-(Q7-C)") (class "Default")
      (node (ref "C27") (pin "2") (pinfunction "2_2") (pintype "passive"))
      (node (ref "Q7") (pin "3") (pinfunction "C_3") (pintype "passive"))
      (node (ref "R56") (pin "2") (pinfunction "2_2") (pintype "passive"))
      (node (ref "R57") (pin "1") (pinfunction "1_1") (pintype "passive"))
    )
    (net (code "94") (name "Net-(R20-Pad2)") (class "Default")
      (node (ref "R20") (pin "2") (pinfunction "2_2") (pintype "passive"))
      (node (ref "SWD1") (pin "2") (pinfunction "2_2") (pintype "passive"))
    )
    (net (code "95") (name "Net-(R23-Pad2)") (class "Default")
      (node (ref "R23") (pin "2") (pinfunction "2_2") (pintype "passive"))
      (node (ref "SWD1") (pin "3") (pinfunction "3_3") (pintype "passive"))
    )
    (net (code "96") (name "Net-(U1A-PD0-OSC_IN)") (class "Default")
      (node (ref "C16") (pin "1") (pinfunction "1_1") (pintype "passive"))
      (node (ref "U1") (pin "5") (pinfunction "PD0-OSC_IN_5") (pintype "bidirectional"))
      (node (ref "X1") (pin "3") (pinfunction "3_3") (pintype "passive"))
    )
    (net (code "97") (name "Net-(U1A-PD1)") (class "Default")
      (node (ref "C17") (pin "1") (pinfunction "1_1") (pintype "passive"))
      (node (ref "U1") (pin "6") (pinfunction "PD1_6") (pintype "bidirectional"))
      (node (ref "X1") (pin "1") (pinfunction "1_1") (pintype "passive"))
    )
    (net (code "98") (name "Net-(U2-BS)") (class "Default")
      (node (ref "C1") (pin "2") (pinfunction "2_2") (pintype "passive"))
      (node (ref "U2") (pin "1") (pinfunction "BS_1") (pintype "passive"))
    )
    (net (code "99") (name "Net-(U2-EN)") (class "Default")
      (node (ref "R3") (pin "2") (pinfunction "2_2") (pintype "passive"))
      (node (ref "U2") (pin "4") (pinfunction "EN_4") (pintype "passive"))
    )
    (net (code "100") (name "Net-(U4-BS)") (class "Default")
      (node (ref "C8") (pin "2") (pinfunction "2_2") (pintype "passive"))
      (node (ref "U4") (pin "1") (pinfunction "BS_1") (pintype "passive"))
    )
    (net (code "101") (name "Net-(U4-EN)") (class "Default")
      (node (ref "R12") (pin "2") (pinfunction "2_2") (pintype "passive"))
      (node (ref "U4") (pin "4") (pinfunction "EN_4") (pintype "passive"))
    )
    (net (code "102") (name "Net-(U5-INNA)") (class "Default")
      (node (ref "C20") (pin "2") (pinfunction "2_2") (pintype "passive"))
      (node (ref "R29") (pin "2") (pinfunction "2_2") (pintype "passive"))
      (node (ref "U5") (pin "7") (pinfunction "INNA_7") (pintype "passive"))
    )
    (net (code "103") (name "Net-(U5-INPA)") (class "Default")
      (node (ref "C20") (pin "1") (pinfunction "1_1") (pintype "passive"))
      (node (ref "R31") (pin "1") (pinfunction "1_1") (pintype "passive"))
      (node (ref "U5") (pin "8") (pinfunction "INPA_8") (pintype "passive"))
    )
    (net (code "104") (name "Net-(U5-RATE)") (class "Default")
      (node (ref "R16") (pin "1") (pinfunction "1_1") (pintype "passive"))
      (node (ref "R18") (pin "1") (pinfunction "1_1") (pintype "passive"))
      (node (ref "U5") (pin "15") (pinfunction "RATE_15") (pintype "passive"))
    )
    (net (code "105") (name "Net-(U5-VBG)") (class "Default")
      (node (ref "C18") (pin "1") (pinfunction "1_1") (pintype "passive"))
      (node (ref "U5") (pin "6") (pinfunction "VBG_6") (pintype "passive"))
    )
    (net (code "106") (name "Net-(U5-VFB)") (class "Default")
      (node (ref "R21") (pin "2") (pinfunction "2_2") (pintype "passive"))
      (node (ref "R25") (pin "2") (pinfunction "2_2") (pintype "passive"))
      (node (ref "U5") (pin "4") (pinfunction "VFB_4") (pintype "passive"))
    )
    (net (code "107") (name "Net-(U6-INNA)") (class "Default")
      (node (ref "C21") (pin "2") (pinfunction "2_2") (pintype "passive"))
      (node (ref "R30") (pin "2") (pinfunction "2_2") (pintype "passive"))
      (node (ref "U6") (pin "7") (pinfunction "INNA_7") (pintype "passive"))
    )
    (net (code "108") (name "Net-(U6-INPA)") (class "Default")
      (node (ref "C21") (pin "1") (pinfunction "1_1") (pintype "passive"))
      (node (ref "R32") (pin "1") (pinfunction "1_1") (pintype "passive"))
      (node (ref "U6") (pin "8") (pinfunction "INPA_8") (pintype "passive"))
    )
    (net (code "109") (name "Net-(U6-RATE)") (class "Default")
      (node (ref "R17") (pin "1") (pinfunction "1_1") (pintype "passive"))
      (node (ref "R19") (pin "1") (pinfunction "1_1") (pintype "passive"))
      (node (ref "U6") (pin "15") (pinfunction "RATE_15") (pintype "passive"))
    )
    (net (code "110") (name "Net-(U6-VBG)") (class "Default")
      (node (ref "C19") (pin "1") (pinfunction "1_1") (pintype "passive"))
      (node (ref "U6") (pin "6") (pinfunction "VBG_6") (pintype "passive"))
    )
    (net (code "111") (name "Net-(U6-VFB)") (class "Default")
      (node (ref "R22") (pin "2") (pinfunction "2_2") (pintype "passive"))
      (node (ref "R26") (pin "2") (pinfunction "2_2") (pintype "passive"))
      (node (ref "U6") (pin "4") (pinfunction "VFB_4") (pintype "passive"))
    )
    (net (code "112") (name "Net-(U6-XI)") (class "Default")
      (node (ref "R19") (pin "2") (pinfunction "2_2") (pintype "passive"))
      (node (ref "U6") (pin "14") (pinfunction "XI_14") (pintype "passive"))
    )
    (net (code "113") (name "Net-(U7-INNA)") (class "Default")
      (node (ref "C24") (pin "2") (pinfunction "2_2") (pintype "passive"))
      (node (ref "R41") (pin "2") (pinfunction "2_2") (pintype "passive"))
      (node (ref "U7") (pin "7") (pinfunction "INNA_7") (pintype "passive"))
    )
    (net (code "114") (name "Net-(U7-INPA)") (class "Default")
      (node (ref "C24") (pin "1") (pinfunction "1_1") (pintype "passive"))
      (node (ref "R43") (pin "1") (pinfunction "1_1") (pintype "passive"))
      (node (ref "U7") (pin "8") (pinfunction "INPA_8") (pintype "passive"))
    )
    (net (code "115") (name "Net-(U7-RATE)") (class "Default")
      (node (ref "R33") (pin "1") (pinfunction "1_1") (pintype "passive"))
      (node (ref "R34") (pin "1") (pinfunction "1_1") (pintype "passive"))
      (node (ref "U7") (pin "15") (pinfunction "RATE_15") (pintype "passive"))
    )
    (net (code "116") (name "Net-(U7-VBG)") (class "Default")
      (node (ref "C22") (pin "1") (pinfunction "1_1") (pintype "passive"))
      (node (ref "U7") (pin "6") (pinfunction "VBG_6") (pintype "passive"))
    )
    (net (code "117") (name "Net-(U7-VFB)") (class "Default")
      (node (ref "R37") (pin "2") (pinfunction "2_2") (pintype "passive"))
      (node (ref "R38") (pin "2") (pinfunction "2_2") (pintype "passive"))
      (node (ref "U7") (pin "4") (pinfunction "VFB_4") (pintype "passive"))
    )
    (net (code "118") (name "Net-(U8-INNA)") (class "Default")
      (node (ref "C25") (pin "2") (pinfunction "2_2") (pintype "passive"))
      (node (ref "R42") (pin "2") (pinfunction "2_2") (pintype "passive"))
      (node (ref "U8") (pin "7") (pinfunction "INNA_7") (pintype "passive"))
    )
    (net (code "119") (name "Net-(U8-INPA)") (class "Default")
      (node (ref "C25") (pin "1") (pinfunction "1_1") (pintype "passive"))
      (node (ref "R44") (pin "1") (pinfunction "1_1") (pintype "passive"))
      (node (ref "U8") (pin "8") (pinfunction "INPA_8") (pintype "passive"))
    )
    (net (code "120") (name "Net-(U8-RATE)") (class "Default")
      (node (ref "R35") (pin "1") (pinfunction "1_1") (pintype "passive"))
      (node (ref "R36") (pin "1") (pinfunction "1_1") (pintype "passive"))
      (node (ref "U8") (pin "15") (pinfunction "RATE_15") (pintype "passive"))
    )
    (net (code "121") (name "Net-(U8-VBG)") (class "Default")
      (node (ref "C23") (pin "1") (pinfunction "1_1") (pintype "passive"))
      (node (ref "U8") (pin "6") (pinfunction "VBG_6") (pintype "passive"))
    )
    (net (code "122") (name "Net-(U8-VFB)") (class "Default")
      (node (ref "R39") (pin "2") (pinfunction "2_2") (pintype "passive"))
      (node (ref "R40") (pin "2") (pinfunction "2_2") (pintype "passive"))
      (node (ref "U8") (pin "4") (pinfunction "VFB_4") (pintype "passive"))
    )
    (net (code "123") (name "Net-(U8-XI)") (class "Default")
      (node (ref "R36") (pin "2") (pinfunction "2_2") (pintype "passive"))
      (node (ref "U8") (pin "14") (pinfunction "XI_14") (pintype "passive"))
    )
    (net (code "124") (name "Net-(U9-RO)") (class "Default")
      (node (ref "R46") (pin "1") (pinfunction "1_1") (pintype "passive"))
      (node (ref "U9") (pin "1") (pinfunction "RO_1") (pintype "passive"))
    )
    (net (code "125") (name "Net-(U11-G)") (class "Default")
      (node (ref "R56") (pin "1") (pinfunction "1_1") (pintype "passive"))
      (node (ref "U11") (pin "4") (pinfunction "G_4") (pintype "passive"))
    )
    (net (code "126") (name "VBAT") (class "Default")
      (node (ref "CN22") (pin "2") (pinfunction "2_2") (pintype "passive"))
      (node (ref "D6") (pin "2") (pinfunction "2_2") (pintype "passive"))
      (node (ref "Q7") (pin "2") (pinfunction "E_2") (pintype "passive"))
      (node (ref "R51") (pin "2") (pinfunction "2_2") (pintype "passive"))
      (node (ref "R52") (pin "2") (pinfunction "2_2") (pintype "passive"))
      (node (ref "R53") (pin "2") (pinfunction "2_2") (pintype "passive"))
      (node (ref "U11") (pin "1") (pinfunction "S_1") (pintype "passive"))
      (node (ref "U11") (pin "2") (pinfunction "S_2") (pintype "passive"))
      (node (ref "U11") (pin "3") (pinfunction "S_3") (pintype "passive"))
    )
    (net (code "127") (name "VCC_3V3") (class "Default")
      (node (ref "C10") (pin "2") (pinfunction "2_2") (pintype "passive"))
      (node (ref "C11") (pin "2") (pinfunction "2_2") (pintype "passive"))
      (node (ref "C12") (pin "2") (pinfunction "2_2") (pintype "passive"))
      (node (ref "C26") (pin "2") (pinfunction "2_2") (pintype "passive"))
      (node (ref "C6") (pin "2") (pinfunction "2_2") (pintype "passive"))
      (node (ref "C9") (pin "2") (pinfunction "2_2") (pintype "passive"))
      (node (ref "Q1") (pin "2") (pinfunction "E_2") (pintype "passive"))
      (node (ref "Q2") (pin "2") (pinfunction "E_2") (pintype "passive"))
      (node (ref "Q3") (pin "2") (pinfunction "E_2") (pintype "passive"))
      (node (ref "Q4") (pin "2") (pinfunction "E_2") (pintype "passive"))
      (node (ref "R1") (pin "2") (pinfunction "2_2") (pintype "passive"))
      (node (ref "R11") (pin "1") (pinfunction "1_1") (pintype "passive"))
      (node (ref "R16") (pin "2") (pinfunction "2_2") (pintype "passive"))
      (node (ref "R17") (pin "2") (pinfunction "2_2") (pintype "passive"))
      (node (ref "R33") (pin "2") (pinfunction "2_2") (pintype "passive"))
      (node (ref "R35") (pin "2") (pinfunction "2_2") (pintype "passive"))
      (node (ref "R45") (pin "2") (pinfunction "2_2") (pintype "passive"))
      (node (ref "R47") (pin "2") (pinfunction "2_2") (pintype "passive"))
      (node (ref "R50") (pin "1") (pinfunction "1_1") (pintype "passive"))
      (node (ref "R7") (pin "1") (pinfunction "1_1") (pintype "passive"))
      (node (ref "R8") (pin "2") (pinfunction "2_2") (pintype "passive"))
      (node (ref "R9") (pin "1") (pinfunction "1_1") (pintype "passive"))
      (node (ref "U1") (pin "1") (pinfunction "VBAT_1") (pintype "power_in"))
      (node (ref "U1") (pin "24") (pinfunction "VDD_1_24") (pintype "power_in"))
      (node (ref "U1") (pin "36") (pinfunction "VDD_2_36") (pintype "power_in"))
      (node (ref "U1") (pin "48") (pinfunction "VDD_3_48") (pintype "power_in"))
      (node (ref "U1") (pin "9") (pinfunction "VDDA_9") (pintype "power_in"))
      (node (ref "U3") (pin "5") (pinfunction "VOUT_5") (pintype "passive"))
      (node (ref "U5") (pin "1") (pinfunction "VSUP_1") (pintype "passive"))
      (node (ref "U5") (pin "16") (pinfunction "DVDD_16") (pintype "passive"))
      (node (ref "U6") (pin "1") (pinfunction "VSUP_1") (pintype "passive"))
      (node (ref "U6") (pin "16") (pinfunction "DVDD_16") (pintype "passive"))
      (node (ref "U7") (pin "1") (pinfunction "VSUP_1") (pintype "passive"))
      (node (ref "U7") (pin "16") (pinfunction "DVDD_16") (pintype "passive"))
      (node (ref "U8") (pin "1") (pinfunction "VSUP_1") (pintype "passive"))
      (node (ref "U8") (pin "16") (pinfunction "DVDD_16") (pintype "passive"))
      (node (ref "U9") (pin "8") (pinfunction "VCC_8") (pintype "passive"))
    )
    (net (code "128") (name "VCC_5V") (class "Default")
      (node (ref "C13") (pin "2") (pinfunction "2_2") (pintype "passive"))
      (node (ref "C14") (pin "2") (pinfunction "2_2") (pintype "passive"))
      (node (ref "C7") (pin "2") (pinfunction "2_2") (pintype "passive"))
      (node (ref "CN17") (pin "1") (pinfunction "1_1") (pintype "passive"))
      (node (ref "CN19") (pin "2") (pinfunction "2_2") (pintype "passive"))
      (node (ref "IC1") (pin "3") (pinfunction "VCC_3") (pintype "passive"))
      (node (ref "L2") (pin "2") (pinfunction "2_2") (pintype "passive"))
      (node (ref "R10") (pin "2") (pinfunction "2_2") (pintype "passive"))
      (node (ref "R14") (pin "1") (pinfunction "1_1") (pintype "passive"))
      (node (ref "SWD1") (pin "4") (pinfunction "4_4") (pintype "passive"))
      (node (ref "U10") (pin "24") (pinfunction "VCC_24") (pintype "passive"))
      (node (ref "U3") (pin "1") (pinfunction "VIN_1") (pintype "passive"))
      (node (ref "U3") (pin "3") (pinfunction "CE_3") (pintype "passive"))
    )
    (net (code "129") (name "VCC_EXTRA_5V") (class "Default")
      (node (ref "C2") (pin "2") (pinfunction "2_2") (pintype "passive"))
      (node (ref "C3") (pin "2") (pinfunction "2_2") (pintype "passive"))
      (node (ref "JP2") (pin "6") (pinfunction "6_6") (pintype "passive"))
      (node (ref "L1") (pin "2") (pinfunction "2_2") (pintype "passive"))
      (node (ref "R15") (pin "1") (pinfunction "1_1") (pintype "passive"))
      (node (ref "R2") (pin "2") (pinfunction "2_2") (pintype "passive"))
    )
    (net (code "130") (name "VIN") (class "Default")
      (node (ref "C15") (pin "2") (pinfunction "2_2") (pintype "passive"))
      (node (ref "C5") (pin "2") (pinfunction "2_2") (pintype "passive"))
      (node (ref "CN1") (pin "1") (pinfunction "1_1") (pintype "passive"))
      (node (ref "CN10") (pin "1") (pinfunction "1_1") (pintype "passive"))
      (node (ref "CN11") (pin "1") (pinfunction "1_1") (pintype "passive"))
      (node (ref "CN12") (pin "1") (pinfunction "1_1") (pintype "passive"))
      (node (ref "CN13") (pin "1") (pinfunction "1_1") (pintype "passive"))
      (node (ref "CN14") (pin "1") (pinfunction "1_1") (pintype "passive"))
      (node (ref "CN15") (pin "1") (pinfunction "1_1") (pintype "passive"))
      (node (ref "CN16") (pin "1") (pinfunction "1_1") (pintype "passive"))
      (node (ref "CN2") (pin "1") (pinfunction "1_1") (pintype "passive"))
      (node (ref "CN3") (pin "1") (pinfunction "1_1") (pintype "passive"))
      (node (ref "CN4") (pin "1") (pinfunction "1_1") (pintype "passive"))
      (node (ref "CN5") (pin "1") (pinfunction "1_1") (pintype "passive"))
      (node (ref "CN6") (pin "1") (pinfunction "1_1") (pintype "passive"))
      (node (ref "CN7") (pin "1") (pinfunction "1_1") (pintype "passive"))
      (node (ref "CN8") (pin "1") (pinfunction "1_1") (pintype "passive"))
      (node (ref "CN9") (pin "1") (pinfunction "1_1") (pintype "passive"))
      (node (ref "R12") (pin "1") (pinfunction "1_1") (pintype "passive"))
      (node (ref "R3") (pin "1") (pinfunction "1_1") (pintype "passive"))
      (node (ref "R55") (pin "1") (pinfunction "1_1") (pintype "passive"))
      (node (ref "U11") (pin "5") (pinfunction "D_5") (pintype "passive"))
      (node (ref "U11") (pin "6") (pinfunction "D_6") (pintype "passive"))
      (node (ref "U11") (pin "7") (pinfunction "D_7") (pintype "passive"))
      (node (ref "U11") (pin "8") (pinfunction "D_8") (pintype "passive"))
      (node (ref "U11") (pin "9") (pinfunction "D_9") (pintype "passive"))
      (node (ref "U2") (pin "5") (pinfunction "IN_5") (pintype "passive"))
      (node (ref "U4") (pin "5") (pinfunction "IN_5") (pintype "passive"))
    )
    (net (code "131") (name "unconnected-(IC1-VREF-Pad5)") (class "Default")
      (node (ref "IC1") (pin "5") (pinfunction "VREF_5") (pintype "passive"))
    )
    (net (code "132") (name "unconnected-(U1A-PA0-WKUP-Pad10)") (class "Default")
      (node (ref "U1") (pin "10") (pinfunction "PA0-WKUP_10") (pintype "bidirectional"))
    )
    (net (code "133") (name "unconnected-(U1A-PA1-Pad11)") (class "Default")
      (node (ref "U1") (pin "11") (pinfunction "PA1_11") (pintype "bidirectional"))
    )
    (net (code "134") (name "unconnected-(U1A-PA9-Pad30)") (class "Default")
      (node (ref "U1") (pin "30") (pinfunction "PA9_30") (pintype "bidirectional"))
    )
    (net (code "135") (name "unconnected-(U1A-PB0-Pad18)") (class "Default")
      (node (ref "U1") (pin "18") (pinfunction "PB0_18") (pintype "bidirectional"))
    )
    (net (code "136") (name "unconnected-(U1A-PB10-Pad21)") (class "Default")
      (node (ref "U1") (pin "21") (pinfunction "PB10_21") (pintype "bidirectional"))
    )
    (net (code "137") (name "unconnected-(U1A-PC13-TAMPER-RTC-Pad2)") (class "Default")
      (node (ref "U1") (pin "2") (pinfunction "PC13-TAMPER-RTC_2") (pintype "bidirectional"))
    )
    (net (code "138") (name "unconnected-(U1A-PC14-OSC32_IN-Pad3)") (class "Default")
      (node (ref "U1") (pin "3") (pinfunction "PC14-OSC32_IN_3") (pintype "bidirectional"))
    )
    (net (code "139") (name "unconnected-(U1A-PC15-OSC32_OUT-Pad4)") (class "Default")
      (node (ref "U1") (pin "4") (pinfunction "PC15-OSC32_OUT_4") (pintype "bidirectional"))
    )
    (net (code "140") (name "unconnected-(U3-NC-Pad4)") (class "Default")
      (node (ref "U3") (pin "4") (pinfunction "NC_4") (pintype "passive"))
    )
    (net (code "141") (name "unconnected-(U5-INNB-Pad9)") (class "Default")
      (node (ref "U5") (pin "9") (pinfunction "INNB_9") (pintype "passive"))
    )
    (net (code "142") (name "unconnected-(U5-INPB-Pad10)") (class "Default")
      (node (ref "U5") (pin "10") (pinfunction "INPB_10") (pintype "passive"))
    )
    (net (code "143") (name "unconnected-(U5-XO-Pad13)") (class "Default")
      (node (ref "U5") (pin "13") (pinfunction "XO_13") (pintype "passive"))
    )
    (net (code "144") (name "unconnected-(U6-INNB-Pad9)") (class "Default")
      (node (ref "U6") (pin "9") (pinfunction "INNB_9") (pintype "passive"))
    )
    (net (code "145") (name "unconnected-(U6-INPB-Pad10)") (class "Default")
      (node (ref "U6") (pin "10") (pinfunction "INPB_10") (pintype "passive"))
    )
    (net (code "146") (name "unconnected-(U6-XO-Pad13)") (class "Default")
      (node (ref "U6") (pin "13") (pinfunction "XO_13") (pintype "passive"))
    )
    (net (code "147") (name "unconnected-(U7-INNB-Pad9)") (class "Default")
      (node (ref "U7") (pin "9") (pinfunction "INNB_9") (pintype "passive"))
    )
    (net (code "148") (name "unconnected-(U7-INPB-Pad10)") (class "Default")
      (node (ref "U7") (pin "10") (pinfunction "INPB_10") (pintype "passive"))
    )
    (net (code "149") (name "unconnected-(U7-XO-Pad13)") (class "Default")
      (node (ref "U7") (pin "13") (pinfunction "XO_13") (pintype "passive"))
    )
    (net (code "150") (name "unconnected-(U8-INNB-Pad9)") (class "Default")
      (node (ref "U8") (pin "9") (pinfunction "INNB_9") (pintype "passive"))
    )
    (net (code "151") (name "unconnected-(U8-INPB-Pad10)") (class "Default")
      (node (ref "U8") (pin "10") (pinfunction "INPB_10") (pintype "passive"))
    )
    (net (code "152") (name "unconnected-(U8-XO-Pad13)") (class "Default")
      (node (ref "U8") (pin "13") (pinfunction "XO_13") (pintype "passive"))
    )
  )
)
